# FD-01_MK3.net
KiCad netlist of a schematic drawn in EasyEDA
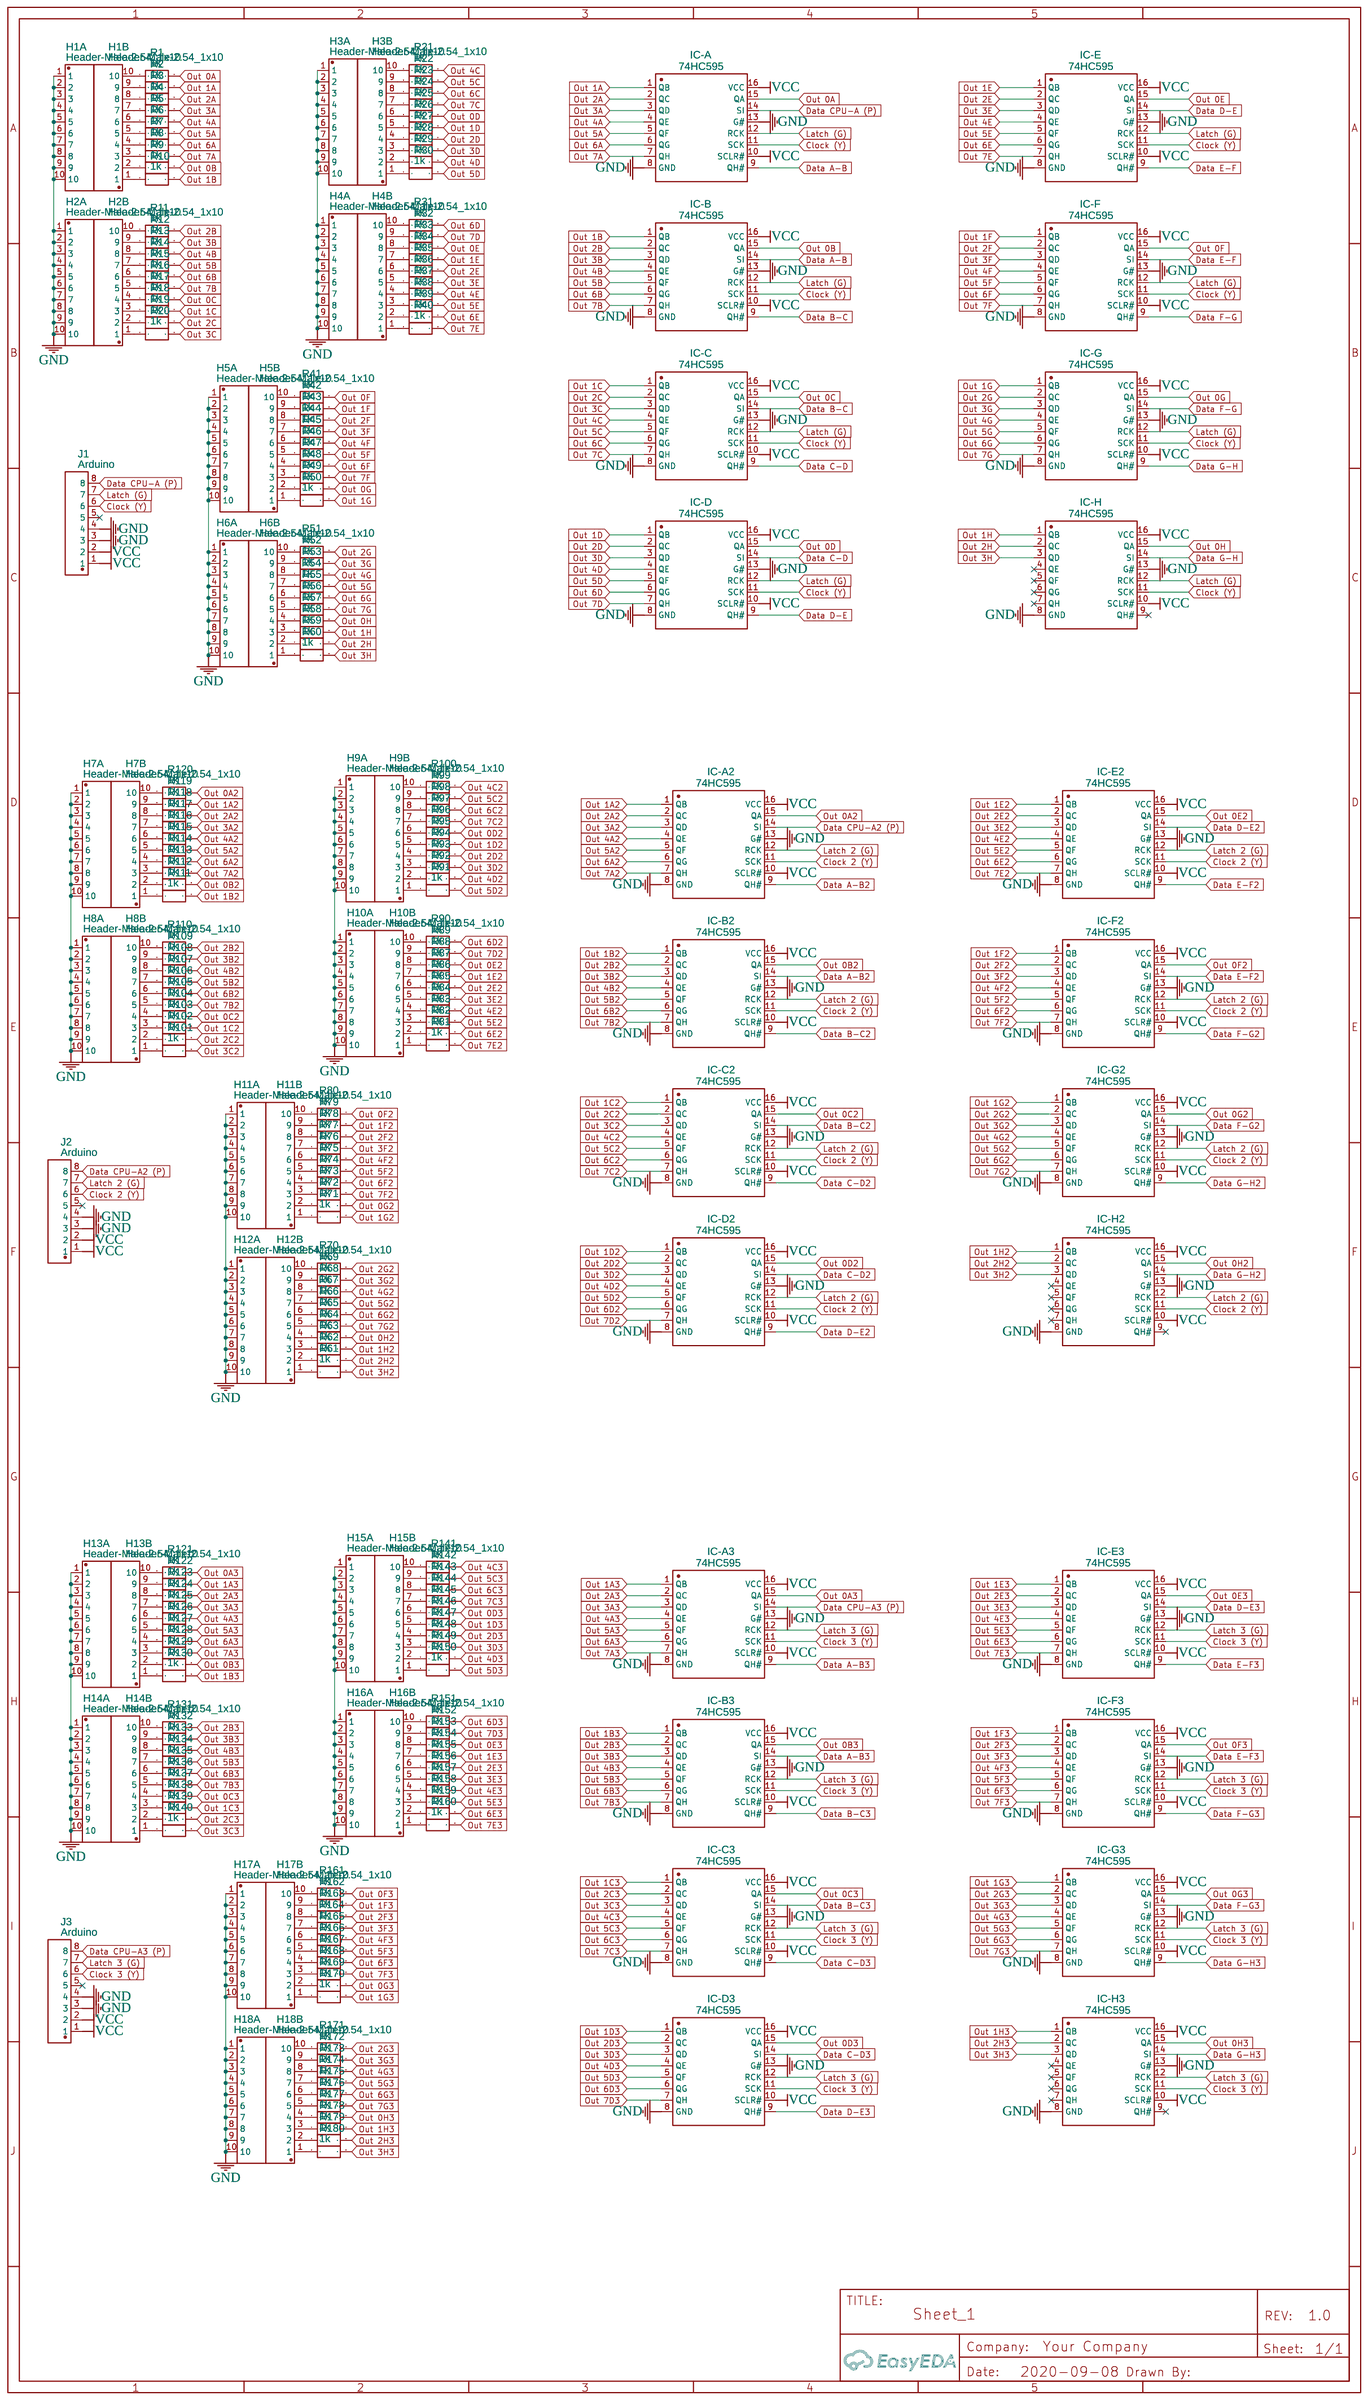
[diagram p0: schematic sheet]

(export (version "E")
  (design (tool "Eeschema 10.0.6"))
  (components
    (comp (ref "H1A")
      (value "Header-Male-2.54_1x10")
      (fields
        (field (name "BOM_Manufacturer Part") "Headers  Pins2.54mm1*10P")
        (field (name "BOM_Supplier Part") "C57369")
      )
      (libsource (lib "") (part "Header-Male-2.54_1x10_16"))
    )
    (comp (ref "H1B")
      (value "Header-Male-2.54_1x10")
      (fields
        (field (name "BOM_Manufacturer Part") "Headers  Pins2.54mm1*10P")
        (field (name "BOM_Supplier Part") "C57369")
      )
      (libsource (lib "") (part "Header-Male-2.54_1x10_34"))
    )
    (comp (ref "H2A")
      (value "Header-Male-2.54_1x10")
      (fields
        (field (name "BOM_Manufacturer Part") "Headers  Pins2.54mm1*10P")
        (field (name "BOM_Supplier Part") "C57369")
      )
      (libsource (lib "") (part "Header-Male-2.54_1x10_31"))
    )
    (comp (ref "H2B")
      (value "Header-Male-2.54_1x10")
      (fields
        (field (name "BOM_Manufacturer Part") "Headers  Pins2.54mm1*10P")
        (field (name "BOM_Supplier Part") "C57369")
      )
      (libsource (lib "") (part "Header-Male-2.54_1x10_8"))
    )
    (comp (ref "H3A")
      (value "Header-Male-2.54_1x10")
      (fields
        (field (name "BOM_Manufacturer Part") "Headers  Pins2.54mm1*10P")
        (field (name "BOM_Supplier Part") "C57369")
      )
      (libsource (lib "") (part "Header-Male-2.54_1x10_15"))
    )
    (comp (ref "H3B")
      (value "Header-Male-2.54_1x10")
      (fields
        (field (name "BOM_Manufacturer Part") "Headers  Pins2.54mm1*10P")
        (field (name "BOM_Supplier Part") "C57369")
      )
      (libsource (lib "") (part "Header-Male-2.54_1x10_9"))
    )
    (comp (ref "H4A")
      (value "Header-Male-2.54_1x10")
      (fields
        (field (name "BOM_Manufacturer Part") "Headers  Pins2.54mm1*10P")
        (field (name "BOM_Supplier Part") "C57369")
      )
      (libsource (lib "") (part "Header-Male-2.54_1x10_23"))
    )
    (comp (ref "H4B")
      (value "Header-Male-2.54_1x10")
      (fields
        (field (name "BOM_Manufacturer Part") "Headers  Pins2.54mm1*10P")
        (field (name "BOM_Supplier Part") "C57369")
      )
      (libsource (lib "") (part "Header-Male-2.54_1x10_27"))
    )
    (comp (ref "H5A")
      (value "Header-Male-2.54_1x10")
      (fields
        (field (name "BOM_Manufacturer Part") "Headers  Pins2.54mm1*10P")
        (field (name "BOM_Supplier Part") "C57369")
      )
      (libsource (lib "") (part "Header-Male-2.54_1x10_22"))
    )
    (comp (ref "H5B")
      (value "Header-Male-2.54_1x10")
      (fields
        (field (name "BOM_Manufacturer Part") "Headers  Pins2.54mm1*10P")
        (field (name "BOM_Supplier Part") "C57369")
      )
      (libsource (lib "") (part "Header-Male-2.54_1x10_19"))
    )
    (comp (ref "H6A")
      (value "Header-Male-2.54_1x10")
      (fields
        (field (name "BOM_Manufacturer Part") "Headers  Pins2.54mm1*10P")
        (field (name "BOM_Supplier Part") "C57369")
      )
      (libsource (lib "") (part "Header-Male-2.54_1x10_25"))
    )
    (comp (ref "H6B")
      (value "Header-Male-2.54_1x10")
      (fields
        (field (name "BOM_Manufacturer Part") "Headers  Pins2.54mm1*10P")
        (field (name "BOM_Supplier Part") "C57369")
      )
      (libsource (lib "") (part "Header-Male-2.54_1x10_24"))
    )
    (comp (ref "H7A")
      (value "Header-Male-2.54_1x10")
      (fields
        (field (name "BOM_Manufacturer Part") "Headers  Pins2.54mm1*10P")
        (field (name "BOM_Supplier Part") "C57369")
      )
      (libsource (lib "") (part "Header-Male-2.54_1x10_30"))
    )
    (comp (ref "H7B")
      (value "Header-Male-2.54_1x10")
      (fields
        (field (name "BOM_Manufacturer Part") "Headers  Pins2.54mm1*10P")
        (field (name "BOM_Supplier Part") "C57369")
      )
      (libsource (lib "") (part "Header-Male-2.54_1x10_29"))
    )
    (comp (ref "H8A")
      (value "Header-Male-2.54_1x10")
      (fields
        (field (name "BOM_Manufacturer Part") "Headers  Pins2.54mm1*10P")
        (field (name "BOM_Supplier Part") "C57369")
      )
      (libsource (lib "") (part "Header-Male-2.54_1x10_32"))
    )
    (comp (ref "H8B")
      (value "Header-Male-2.54_1x10")
      (fields
        (field (name "BOM_Manufacturer Part") "Headers  Pins2.54mm1*10P")
        (field (name "BOM_Supplier Part") "C57369")
      )
      (libsource (lib "") (part "Header-Male-2.54_1x10_21"))
    )
    (comp (ref "H9A")
      (value "Header-Male-2.54_1x10")
      (fields
        (field (name "BOM_Manufacturer Part") "Headers  Pins2.54mm1*10P")
        (field (name "BOM_Supplier Part") "C57369")
      )
      (libsource (lib "") (part "Header-Male-2.54_1x10_13"))
    )
    (comp (ref "H9B")
      (value "Header-Male-2.54_1x10")
      (fields
        (field (name "BOM_Manufacturer Part") "Headers  Pins2.54mm1*10P")
        (field (name "BOM_Supplier Part") "C57369")
      )
      (libsource (lib "") (part "Header-Male-2.54_1x10_33"))
    )
    (comp (ref "H10A")
      (value "Header-Male-2.54_1x10")
      (fields
        (field (name "BOM_Manufacturer Part") "Headers  Pins2.54mm1*10P")
        (field (name "BOM_Supplier Part") "C57369")
      )
      (libsource (lib "") (part "Header-Male-2.54_1x10"))
    )
    (comp (ref "H10B")
      (value "Header-Male-2.54_1x10")
      (fields
        (field (name "BOM_Manufacturer Part") "Headers  Pins2.54mm1*10P")
        (field (name "BOM_Supplier Part") "C57369")
      )
      (libsource (lib "") (part "Header-Male-2.54_1x10_18"))
    )
    (comp (ref "H11A")
      (value "Header-Male-2.54_1x10")
      (fields
        (field (name "BOM_Manufacturer Part") "Headers  Pins2.54mm1*10P")
        (field (name "BOM_Supplier Part") "C57369")
      )
      (libsource (lib "") (part "Header-Male-2.54_1x10_1"))
    )
    (comp (ref "H11B")
      (value "Header-Male-2.54_1x10")
      (fields
        (field (name "BOM_Manufacturer Part") "Headers  Pins2.54mm1*10P")
        (field (name "BOM_Supplier Part") "C57369")
      )
      (libsource (lib "") (part "Header-Male-2.54_1x10_26"))
    )
    (comp (ref "H12A")
      (value "Header-Male-2.54_1x10")
      (fields
        (field (name "BOM_Manufacturer Part") "Headers  Pins2.54mm1*10P")
        (field (name "BOM_Supplier Part") "C57369")
      )
      (libsource (lib "") (part "Header-Male-2.54_1x10_5"))
    )
    (comp (ref "H12B")
      (value "Header-Male-2.54_1x10")
      (fields
        (field (name "BOM_Manufacturer Part") "Headers  Pins2.54mm1*10P")
        (field (name "BOM_Supplier Part") "C57369")
      )
      (libsource (lib "") (part "Header-Male-2.54_1x10_6"))
    )
    (comp (ref "H13A")
      (value "Header-Male-2.54_1x10")
      (fields
        (field (name "BOM_Manufacturer Part") "Headers  Pins2.54mm1*10P")
        (field (name "BOM_Supplier Part") "C57369")
      )
      (libsource (lib "") (part "Header-Male-2.54_1x10_20"))
    )
    (comp (ref "H13B")
      (value "Header-Male-2.54_1x10")
      (fields
        (field (name "BOM_Manufacturer Part") "Headers  Pins2.54mm1*10P")
        (field (name "BOM_Supplier Part") "C57369")
      )
      (libsource (lib "") (part "Header-Male-2.54_1x10_7"))
    )
    (comp (ref "H14A")
      (value "Header-Male-2.54_1x10")
      (fields
        (field (name "BOM_Manufacturer Part") "Headers  Pins2.54mm1*10P")
        (field (name "BOM_Supplier Part") "C57369")
      )
      (libsource (lib "") (part "Header-Male-2.54_1x10_35"))
    )
    (comp (ref "H14B")
      (value "Header-Male-2.54_1x10")
      (fields
        (field (name "BOM_Manufacturer Part") "Headers  Pins2.54mm1*10P")
        (field (name "BOM_Supplier Part") "C57369")
      )
      (libsource (lib "") (part "Header-Male-2.54_1x10_4"))
    )
    (comp (ref "H15A")
      (value "Header-Male-2.54_1x10")
      (fields
        (field (name "BOM_Manufacturer Part") "Headers  Pins2.54mm1*10P")
        (field (name "BOM_Supplier Part") "C57369")
      )
      (libsource (lib "") (part "Header-Male-2.54_1x10_12"))
    )
    (comp (ref "H15B")
      (value "Header-Male-2.54_1x10")
      (fields
        (field (name "BOM_Manufacturer Part") "Headers  Pins2.54mm1*10P")
        (field (name "BOM_Supplier Part") "C57369")
      )
      (libsource (lib "") (part "Header-Male-2.54_1x10_14"))
    )
    (comp (ref "H16A")
      (value "Header-Male-2.54_1x10")
      (fields
        (field (name "BOM_Manufacturer Part") "Headers  Pins2.54mm1*10P")
        (field (name "BOM_Supplier Part") "C57369")
      )
      (libsource (lib "") (part "Header-Male-2.54_1x10_11"))
    )
    (comp (ref "H16B")
      (value "Header-Male-2.54_1x10")
      (fields
        (field (name "BOM_Manufacturer Part") "Headers  Pins2.54mm1*10P")
        (field (name "BOM_Supplier Part") "C57369")
      )
      (libsource (lib "") (part "Header-Male-2.54_1x10_10"))
    )
    (comp (ref "H17A")
      (value "Header-Male-2.54_1x10")
      (fields
        (field (name "BOM_Manufacturer Part") "Headers  Pins2.54mm1*10P")
        (field (name "BOM_Supplier Part") "C57369")
      )
      (libsource (lib "") (part "Header-Male-2.54_1x10_3"))
    )
    (comp (ref "H17B")
      (value "Header-Male-2.54_1x10")
      (fields
        (field (name "BOM_Manufacturer Part") "Headers  Pins2.54mm1*10P")
        (field (name "BOM_Supplier Part") "C57369")
      )
      (libsource (lib "") (part "Header-Male-2.54_1x10_28"))
    )
    (comp (ref "H18A")
      (value "Header-Male-2.54_1x10")
      (fields
        (field (name "BOM_Manufacturer Part") "Headers  Pins2.54mm1*10P")
        (field (name "BOM_Supplier Part") "C57369")
      )
      (libsource (lib "") (part "Header-Male-2.54_1x10_17"))
    )
    (comp (ref "H18B")
      (value "Header-Male-2.54_1x10")
      (fields
        (field (name "BOM_Manufacturer Part") "Headers  Pins2.54mm1*10P")
        (field (name "BOM_Supplier Part") "C57369")
      )
      (libsource (lib "") (part "Header-Male-2.54_1x10_2"))
    )
    (comp (ref "IC-A")
      (value "74HC595")
      (fields (field (name "BOM_Manufacturer Part") "74HC595D") (field (name "BOM_Supplier Part") "C86609"))
      (libsource (lib "") (part "74HC595D_7"))
    )
    (comp (ref "IC-A2")
      (value "74HC595")
      (fields (field (name "BOM_Manufacturer Part") "74HC595D") (field (name "BOM_Supplier Part") "C86609"))
      (libsource (lib "") (part "74HC595D_7"))
    )
    (comp (ref "IC-A3")
      (value "74HC595")
      (fields (field (name "BOM_Manufacturer Part") "74HC595D") (field (name "BOM_Supplier Part") "C86609"))
      (libsource (lib "") (part "74HC595D_7"))
    )
    (comp (ref "IC-B")
      (value "74HC595")
      (fields (field (name "BOM_Manufacturer Part") "74HC595D") (field (name "BOM_Supplier Part") "C86609"))
      (libsource (lib "") (part "74HC595D_6"))
    )
    (comp (ref "IC-B2")
      (value "74HC595")
      (fields (field (name "BOM_Manufacturer Part") "74HC595D") (field (name "BOM_Supplier Part") "C86609"))
      (libsource (lib "") (part "74HC595D_6"))
    )
    (comp (ref "IC-B3")
      (value "74HC595")
      (fields (field (name "BOM_Manufacturer Part") "74HC595D") (field (name "BOM_Supplier Part") "C86609"))
      (libsource (lib "") (part "74HC595D_6"))
    )
    (comp (ref "IC-C")
      (value "74HC595")
      (fields (field (name "BOM_Manufacturer Part") "74HC595D") (field (name "BOM_Supplier Part") "C86609"))
      (libsource (lib "") (part "74HC595D_2"))
    )
    (comp (ref "IC-C2")
      (value "74HC595")
      (fields (field (name "BOM_Manufacturer Part") "74HC595D") (field (name "BOM_Supplier Part") "C86609"))
      (libsource (lib "") (part "74HC595D_2"))
    )
    (comp (ref "IC-C3")
      (value "74HC595")
      (fields (field (name "BOM_Manufacturer Part") "74HC595D") (field (name "BOM_Supplier Part") "C86609"))
      (libsource (lib "") (part "74HC595D_2"))
    )
    (comp (ref "IC-D")
      (value "74HC595")
      (fields (field (name "BOM_Manufacturer Part") "74HC595D") (field (name "BOM_Supplier Part") "C86609"))
      (libsource (lib "") (part "74HC595D_3"))
    )
    (comp (ref "IC-D2")
      (value "74HC595")
      (fields (field (name "BOM_Manufacturer Part") "74HC595D") (field (name "BOM_Supplier Part") "C86609"))
      (libsource (lib "") (part "74HC595D_3"))
    )
    (comp (ref "IC-D3")
      (value "74HC595")
      (fields (field (name "BOM_Manufacturer Part") "74HC595D") (field (name "BOM_Supplier Part") "C86609"))
      (libsource (lib "") (part "74HC595D_3"))
    )
    (comp (ref "IC-E")
      (value "74HC595")
      (fields (field (name "BOM_Manufacturer Part") "74HC595D") (field (name "BOM_Supplier Part") "C86609"))
      (libsource (lib "") (part "74HC595D"))
    )
    (comp (ref "IC-E2")
      (value "74HC595")
      (fields (field (name "BOM_Manufacturer Part") "74HC595D") (field (name "BOM_Supplier Part") "C86609"))
      (libsource (lib "") (part "74HC595D"))
    )
    (comp (ref "IC-E3")
      (value "74HC595")
      (fields (field (name "BOM_Manufacturer Part") "74HC595D") (field (name "BOM_Supplier Part") "C86609"))
      (libsource (lib "") (part "74HC595D"))
    )
    (comp (ref "IC-F")
      (value "74HC595")
      (fields (field (name "BOM_Manufacturer Part") "74HC595D") (field (name "BOM_Supplier Part") "C86609"))
      (libsource (lib "") (part "74HC595D_1"))
    )
    (comp (ref "IC-F2")
      (value "74HC595")
      (fields (field (name "BOM_Manufacturer Part") "74HC595D") (field (name "BOM_Supplier Part") "C86609"))
      (libsource (lib "") (part "74HC595D_1"))
    )
    (comp (ref "IC-F3")
      (value "74HC595")
      (fields (field (name "BOM_Manufacturer Part") "74HC595D") (field (name "BOM_Supplier Part") "C86609"))
      (libsource (lib "") (part "74HC595D_1"))
    )
    (comp (ref "IC-G")
      (value "74HC595")
      (fields (field (name "BOM_Manufacturer Part") "74HC595D") (field (name "BOM_Supplier Part") "C86609"))
      (libsource (lib "") (part "74HC595D_4"))
    )
    (comp (ref "IC-G2")
      (value "74HC595")
      (fields (field (name "BOM_Manufacturer Part") "74HC595D") (field (name "BOM_Supplier Part") "C86609"))
      (libsource (lib "") (part "74HC595D_4"))
    )
    (comp (ref "IC-G3")
      (value "74HC595")
      (fields (field (name "BOM_Manufacturer Part") "74HC595D") (field (name "BOM_Supplier Part") "C86609"))
      (libsource (lib "") (part "74HC595D_4"))
    )
    (comp (ref "IC-H")
      (value "74HC595")
      (fields (field (name "BOM_Manufacturer Part") "74HC595D") (field (name "BOM_Supplier Part") "C86609"))
      (libsource (lib "") (part "74HC595D_5"))
    )
    (comp (ref "IC-H2")
      (value "74HC595")
      (fields (field (name "BOM_Manufacturer Part") "74HC595D") (field (name "BOM_Supplier Part") "C86609"))
      (libsource (lib "") (part "74HC595D_5"))
    )
    (comp (ref "IC-H3")
      (value "74HC595")
      (fields (field (name "BOM_Manufacturer Part") "74HC595D") (field (name "BOM_Supplier Part") "C86609"))
      (libsource (lib "") (part "74HC595D_5"))
    )
    (comp (ref "J1")
      (value "Arduino")
      (fields
        (field (name "BOM_Manufacturer Part") "Header2.54mm 1*8P")
        (field (name "BOM_Supplier Part") "C49256")
      )
      (libsource (lib "") (part "Header2.54mm 1*8P"))
    )
    (comp (ref "J2")
      (value "Arduino")
      (fields
        (field (name "BOM_Manufacturer Part") "Header2.54mm 1*8P")
        (field (name "BOM_Supplier Part") "C49256")
      )
      (libsource (lib "") (part "Header2.54mm 1*8P"))
    )
    (comp (ref "J3")
      (value "Arduino")
      (fields
        (field (name "BOM_Manufacturer Part") "Header2.54mm 1*8P")
        (field (name "BOM_Supplier Part") "C49256")
      )
      (libsource (lib "") (part "Header2.54mm 1*8P"))
    )
    (comp (ref "R1") (value "1k") (libsource (lib "") (part "R_0603_EU")))
    (comp (ref "R2") (value "1k") (libsource (lib "") (part "R_0603_EU")))
    (comp (ref "R3") (value "1k") (libsource (lib "") (part "R_0603_EU")))
    (comp (ref "R4") (value "1k") (libsource (lib "") (part "R_0603_EU")))
    (comp (ref "R5") (value "1k") (libsource (lib "") (part "R_0603_EU")))
    (comp (ref "R6") (value "1k") (libsource (lib "") (part "R_0603_EU")))
    (comp (ref "R7") (value "1k") (libsource (lib "") (part "R_0603_EU")))
    (comp (ref "R8") (value "1k") (libsource (lib "") (part "R_0603_EU")))
    (comp (ref "R9") (value "1k") (libsource (lib "") (part "R_0603_EU")))
    (comp (ref "R10") (value "1k") (libsource (lib "") (part "R_0603_EU")))
    (comp (ref "R11") (value "1k") (libsource (lib "") (part "R_0603_EU")))
    (comp (ref "R12") (value "1k") (libsource (lib "") (part "R_0603_EU")))
    (comp (ref "R13") (value "1k") (libsource (lib "") (part "R_0603_EU")))
    (comp (ref "R14") (value "1k") (libsource (lib "") (part "R_0603_EU")))
    (comp (ref "R15") (value "1k") (libsource (lib "") (part "R_0603_EU")))
    (comp (ref "R16") (value "1k") (libsource (lib "") (part "R_0603_EU")))
    (comp (ref "R17") (value "1k") (libsource (lib "") (part "R_0603_EU")))
    (comp (ref "R18") (value "1k") (libsource (lib "") (part "R_0603_EU")))
    (comp (ref "R19") (value "1k") (libsource (lib "") (part "R_0603_EU")))
    (comp (ref "R20") (value "1k") (libsource (lib "") (part "R_0603_EU")))
    (comp (ref "R21") (value "1k") (libsource (lib "") (part "R_0603_EU")))
    (comp (ref "R22") (value "1k") (libsource (lib "") (part "R_0603_EU")))
    (comp (ref "R23") (value "1k") (libsource (lib "") (part "R_0603_EU")))
    (comp (ref "R24") (value "1k") (libsource (lib "") (part "R_0603_EU")))
    (comp (ref "R25") (value "1k") (libsource (lib "") (part "R_0603_EU")))
    (comp (ref "R26") (value "1k") (libsource (lib "") (part "R_0603_EU")))
    (comp (ref "R27") (value "1k") (libsource (lib "") (part "R_0603_EU")))
    (comp (ref "R28") (value "1k") (libsource (lib "") (part "R_0603_EU")))
    (comp (ref "R29") (value "1k") (libsource (lib "") (part "R_0603_EU")))
    (comp (ref "R30") (value "1k") (libsource (lib "") (part "R_0603_EU")))
    (comp (ref "R31") (value "1k") (libsource (lib "") (part "R_0603_EU")))
    (comp (ref "R32") (value "1k") (libsource (lib "") (part "R_0603_EU")))
    (comp (ref "R33") (value "1k") (libsource (lib "") (part "R_0603_EU")))
    (comp (ref "R34") (value "1k") (libsource (lib "") (part "R_0603_EU")))
    (comp (ref "R35") (value "1k") (libsource (lib "") (part "R_0603_EU")))
    (comp (ref "R36") (value "1k") (libsource (lib "") (part "R_0603_EU")))
    (comp (ref "R37") (value "1k") (libsource (lib "") (part "R_0603_EU")))
    (comp (ref "R38") (value "1k") (libsource (lib "") (part "R_0603_EU")))
    (comp (ref "R39") (value "1k") (libsource (lib "") (part "R_0603_EU")))
    (comp (ref "R40") (value "1k") (libsource (lib "") (part "R_0603_EU")))
    (comp (ref "R41") (value "1k") (libsource (lib "") (part "R_0603_EU")))
    (comp (ref "R42") (value "1k") (libsource (lib "") (part "R_0603_EU")))
    (comp (ref "R43") (value "1k") (libsource (lib "") (part "R_0603_EU")))
    (comp (ref "R44") (value "1k") (libsource (lib "") (part "R_0603_EU")))
    (comp (ref "R45") (value "1k") (libsource (lib "") (part "R_0603_EU")))
    (comp (ref "R46") (value "1k") (libsource (lib "") (part "R_0603_EU")))
    (comp (ref "R47") (value "1k") (libsource (lib "") (part "R_0603_EU")))
    (comp (ref "R48") (value "1k") (libsource (lib "") (part "R_0603_EU")))
    (comp (ref "R49") (value "1k") (libsource (lib "") (part "R_0603_EU")))
    (comp (ref "R50") (value "1k") (libsource (lib "") (part "R_0603_EU")))
    (comp (ref "R51") (value "1k") (libsource (lib "") (part "R_0603_EU")))
    (comp (ref "R52") (value "1k") (libsource (lib "") (part "R_0603_EU")))
    (comp (ref "R53") (value "1k") (libsource (lib "") (part "R_0603_EU")))
    (comp (ref "R54") (value "1k") (libsource (lib "") (part "R_0603_EU")))
    (comp (ref "R55") (value "1k") (libsource (lib "") (part "R_0603_EU")))
    (comp (ref "R56") (value "1k") (libsource (lib "") (part "R_0603_EU")))
    (comp (ref "R57") (value "1k") (libsource (lib "") (part "R_0603_EU")))
    (comp (ref "R58") (value "1k") (libsource (lib "") (part "R_0603_EU")))
    (comp (ref "R59") (value "1k") (libsource (lib "") (part "R_0603_EU")))
    (comp (ref "R60") (value "1k") (libsource (lib "") (part "R_0603_EU")))
    (comp (ref "R61") (value "1k") (libsource (lib "") (part "R_0603_EU")))
    (comp (ref "R62") (value "1k") (libsource (lib "") (part "R_0603_EU")))
    (comp (ref "R63") (value "1k") (libsource (lib "") (part "R_0603_EU")))
    (comp (ref "R64") (value "1k") (libsource (lib "") (part "R_0603_EU")))
    (comp (ref "R65") (value "1k") (libsource (lib "") (part "R_0603_EU")))
    (comp (ref "R66") (value "1k") (libsource (lib "") (part "R_0603_EU")))
    (comp (ref "R67") (value "1k") (libsource (lib "") (part "R_0603_EU")))
    (comp (ref "R68") (value "1k") (libsource (lib "") (part "R_0603_EU")))
    (comp (ref "R69") (value "1k") (libsource (lib "") (part "R_0603_EU")))
    (comp (ref "R70") (value "1k") (libsource (lib "") (part "R_0603_EU")))
    (comp (ref "R71") (value "1k") (libsource (lib "") (part "R_0603_EU")))
    (comp (ref "R72") (value "1k") (libsource (lib "") (part "R_0603_EU")))
    (comp (ref "R73") (value "1k") (libsource (lib "") (part "R_0603_EU")))
    (comp (ref "R74") (value "1k") (libsource (lib "") (part "R_0603_EU")))
    (comp (ref "R75") (value "1k") (libsource (lib "") (part "R_0603_EU")))
    (comp (ref "R76") (value "1k") (libsource (lib "") (part "R_0603_EU")))
    (comp (ref "R77") (value "1k") (libsource (lib "") (part "R_0603_EU")))
    (comp (ref "R78") (value "1k") (libsource (lib "") (part "R_0603_EU")))
    (comp (ref "R79") (value "1k") (libsource (lib "") (part "R_0603_EU")))
    (comp (ref "R80") (value "1k") (libsource (lib "") (part "R_0603_EU")))
    (comp (ref "R81") (value "1k") (libsource (lib "") (part "R_0603_EU")))
    (comp (ref "R82") (value "1k") (libsource (lib "") (part "R_0603_EU")))
    (comp (ref "R83") (value "1k") (libsource (lib "") (part "R_0603_EU")))
    (comp (ref "R84") (value "1k") (libsource (lib "") (part "R_0603_EU")))
    (comp (ref "R85") (value "1k") (libsource (lib "") (part "R_0603_EU")))
    (comp (ref "R86") (value "1k") (libsource (lib "") (part "R_0603_EU")))
    (comp (ref "R87") (value "1k") (libsource (lib "") (part "R_0603_EU")))
    (comp (ref "R88") (value "1k") (libsource (lib "") (part "R_0603_EU")))
    (comp (ref "R89") (value "1k") (libsource (lib "") (part "R_0603_EU")))
    (comp (ref "R90") (value "1k") (libsource (lib "") (part "R_0603_EU")))
    (comp (ref "R91") (value "1k") (libsource (lib "") (part "R_0603_EU")))
    (comp (ref "R92") (value "1k") (libsource (lib "") (part "R_0603_EU")))
    (comp (ref "R93") (value "1k") (libsource (lib "") (part "R_0603_EU")))
    (comp (ref "R94") (value "1k") (libsource (lib "") (part "R_0603_EU")))
    (comp (ref "R95") (value "1k") (libsource (lib "") (part "R_0603_EU")))
    (comp (ref "R96") (value "1k") (libsource (lib "") (part "R_0603_EU")))
    (comp (ref "R97") (value "1k") (libsource (lib "") (part "R_0603_EU")))
    (comp (ref "R98") (value "1k") (libsource (lib "") (part "R_0603_EU")))
    (comp (ref "R99") (value "1k") (libsource (lib "") (part "R_0603_EU")))
    (comp (ref "R100") (value "1k") (libsource (lib "") (part "R_0603_EU")))
    (comp (ref "R101") (value "1k") (libsource (lib "") (part "R_0603_EU")))
    (comp (ref "R102") (value "1k") (libsource (lib "") (part "R_0603_EU")))
    (comp (ref "R103") (value "1k") (libsource (lib "") (part "R_0603_EU")))
    (comp (ref "R104") (value "1k") (libsource (lib "") (part "R_0603_EU")))
    (comp (ref "R105") (value "1k") (libsource (lib "") (part "R_0603_EU")))
    (comp (ref "R106") (value "1k") (libsource (lib "") (part "R_0603_EU")))
    (comp (ref "R107") (value "1k") (libsource (lib "") (part "R_0603_EU")))
    (comp (ref "R108") (value "1k") (libsource (lib "") (part "R_0603_EU")))
    (comp (ref "R109") (value "1k") (libsource (lib "") (part "R_0603_EU")))
    (comp (ref "R110") (value "1k") (libsource (lib "") (part "R_0603_EU")))
    (comp (ref "R111") (value "1k") (libsource (lib "") (part "R_0603_EU")))
    (comp (ref "R112") (value "1k") (libsource (lib "") (part "R_0603_EU")))
    (comp (ref "R113") (value "1k") (libsource (lib "") (part "R_0603_EU")))
    (comp (ref "R114") (value "1k") (libsource (lib "") (part "R_0603_EU")))
    (comp (ref "R115") (value "1k") (libsource (lib "") (part "R_0603_EU")))
    (comp (ref "R116") (value "1k") (libsource (lib "") (part "R_0603_EU")))
    (comp (ref "R117") (value "1k") (libsource (lib "") (part "R_0603_EU")))
    (comp (ref "R118") (value "1k") (libsource (lib "") (part "R_0603_EU")))
    (comp (ref "R119") (value "1k") (libsource (lib "") (part "R_0603_EU")))
    (comp (ref "R120") (value "1k") (libsource (lib "") (part "R_0603_EU")))
    (comp (ref "R121") (value "1k") (libsource (lib "") (part "R_0603_EU")))
    (comp (ref "R122") (value "1k") (libsource (lib "") (part "R_0603_EU")))
    (comp (ref "R123") (value "1k") (libsource (lib "") (part "R_0603_EU")))
    (comp (ref "R124") (value "1k") (libsource (lib "") (part "R_0603_EU")))
    (comp (ref "R125") (value "1k") (libsource (lib "") (part "R_0603_EU")))
    (comp (ref "R126") (value "1k") (libsource (lib "") (part "R_0603_EU")))
    (comp (ref "R127") (value "1k") (libsource (lib "") (part "R_0603_EU")))
    (comp (ref "R128") (value "1k") (libsource (lib "") (part "R_0603_EU")))
    (comp (ref "R129") (value "1k") (libsource (lib "") (part "R_0603_EU")))
    (comp (ref "R130") (value "1k") (libsource (lib "") (part "R_0603_EU")))
    (comp (ref "R131") (value "1k") (libsource (lib "") (part "R_0603_EU")))
    (comp (ref "R132") (value "1k") (libsource (lib "") (part "R_0603_EU")))
    (comp (ref "R133") (value "1k") (libsource (lib "") (part "R_0603_EU")))
    (comp (ref "R134") (value "1k") (libsource (lib "") (part "R_0603_EU")))
    (comp (ref "R135") (value "1k") (libsource (lib "") (part "R_0603_EU")))
    (comp (ref "R136") (value "1k") (libsource (lib "") (part "R_0603_EU")))
    (comp (ref "R137") (value "1k") (libsource (lib "") (part "R_0603_EU")))
    (comp (ref "R138") (value "1k") (libsource (lib "") (part "R_0603_EU")))
    (comp (ref "R139") (value "1k") (libsource (lib "") (part "R_0603_EU")))
    (comp (ref "R140") (value "1k") (libsource (lib "") (part "R_0603_EU")))
    (comp (ref "R141") (value "1k") (libsource (lib "") (part "R_0603_EU")))
    (comp (ref "R142") (value "1k") (libsource (lib "") (part "R_0603_EU")))
    (comp (ref "R143") (value "1k") (libsource (lib "") (part "R_0603_EU")))
    (comp (ref "R144") (value "1k") (libsource (lib "") (part "R_0603_EU")))
    (comp (ref "R145") (value "1k") (libsource (lib "") (part "R_0603_EU")))
    (comp (ref "R146") (value "1k") (libsource (lib "") (part "R_0603_EU")))
    (comp (ref "R147") (value "1k") (libsource (lib "") (part "R_0603_EU")))
    (comp (ref "R148") (value "1k") (libsource (lib "") (part "R_0603_EU")))
    (comp (ref "R149") (value "1k") (libsource (lib "") (part "R_0603_EU")))
    (comp (ref "R150") (value "1k") (libsource (lib "") (part "R_0603_EU")))
    (comp (ref "R151") (value "1k") (libsource (lib "") (part "R_0603_EU")))
    (comp (ref "R152") (value "1k") (libsource (lib "") (part "R_0603_EU")))
    (comp (ref "R153") (value "1k") (libsource (lib "") (part "R_0603_EU")))
    (comp (ref "R154") (value "1k") (libsource (lib "") (part "R_0603_EU")))
    (comp (ref "R155") (value "1k") (libsource (lib "") (part "R_0603_EU")))
    (comp (ref "R156") (value "1k") (libsource (lib "") (part "R_0603_EU")))
    (comp (ref "R157") (value "1k") (libsource (lib "") (part "R_0603_EU")))
    (comp (ref "R158") (value "1k") (libsource (lib "") (part "R_0603_EU")))
    (comp (ref "R159") (value "1k") (libsource (lib "") (part "R_0603_EU")))
    (comp (ref "R160") (value "1k") (libsource (lib "") (part "R_0603_EU")))
    (comp (ref "R161") (value "1k") (libsource (lib "") (part "R_0603_EU")))
    (comp (ref "R162") (value "1k") (libsource (lib "") (part "R_0603_EU")))
    (comp (ref "R163") (value "1k") (libsource (lib "") (part "R_0603_EU")))
    (comp (ref "R164") (value "1k") (libsource (lib "") (part "R_0603_EU")))
    (comp (ref "R165") (value "1k") (libsource (lib "") (part "R_0603_EU")))
    (comp (ref "R166") (value "1k") (libsource (lib "") (part "R_0603_EU")))
    (comp (ref "R167") (value "1k") (libsource (lib "") (part "R_0603_EU")))
    (comp (ref "R168") (value "1k") (libsource (lib "") (part "R_0603_EU")))
    (comp (ref "R169") (value "1k") (libsource (lib "") (part "R_0603_EU")))
    (comp (ref "R170") (value "1k") (libsource (lib "") (part "R_0603_EU")))
    (comp (ref "R171") (value "1k") (libsource (lib "") (part "R_0603_EU")))
    (comp (ref "R172") (value "1k") (libsource (lib "") (part "R_0603_EU")))
    (comp (ref "R173") (value "1k") (libsource (lib "") (part "R_0603_EU")))
    (comp (ref "R174") (value "1k") (libsource (lib "") (part "R_0603_EU")))
    (comp (ref "R175") (value "1k") (libsource (lib "") (part "R_0603_EU")))
    (comp (ref "R176") (value "1k") (libsource (lib "") (part "R_0603_EU")))
    (comp (ref "R177") (value "1k") (libsource (lib "") (part "R_0603_EU")))
    (comp (ref "R178") (value "1k") (libsource (lib "") (part "R_0603_EU")))
    (comp (ref "R179") (value "1k") (libsource (lib "") (part "R_0603_EU")))
    (comp (ref "R180") (value "1k") (libsource (lib "") (part "R_0603_EU")))
  )
  (nets
    (net (code "1") (name "Clock (Y)") (class "Default")
      (node (ref "IC-A") (pin "11") (pinfunction "SCK_11") (pintype "unspecified"))
      (node (ref "IC-B") (pin "11") (pinfunction "SCK_11") (pintype "unspecified"))
      (node (ref "IC-C") (pin "11") (pinfunction "SCK_11") (pintype "unspecified"))
      (node (ref "IC-D") (pin "11") (pinfunction "SCK_11") (pintype "unspecified"))
      (node (ref "IC-E") (pin "11") (pinfunction "SCK_11") (pintype "unspecified"))
      (node (ref "IC-F") (pin "11") (pinfunction "SCK_11") (pintype "unspecified"))
      (node (ref "IC-G") (pin "11") (pinfunction "SCK_11") (pintype "unspecified"))
      (node (ref "IC-H") (pin "11") (pinfunction "SCK_11") (pintype "unspecified"))
      (node (ref "J1") (pin "6") (pinfunction "6_6") (pintype "unspecified"))
    )
    (net (code "2") (name "Clock 2 (Y)") (class "Default")
      (node (ref "IC-A2") (pin "11") (pinfunction "SCK_11") (pintype "unspecified"))
      (node (ref "IC-B2") (pin "11") (pinfunction "SCK_11") (pintype "unspecified"))
      (node (ref "IC-C2") (pin "11") (pinfunction "SCK_11") (pintype "unspecified"))
      (node (ref "IC-D2") (pin "11") (pinfunction "SCK_11") (pintype "unspecified"))
      (node (ref "IC-E2") (pin "11") (pinfunction "SCK_11") (pintype "unspecified"))
      (node (ref "IC-F2") (pin "11") (pinfunction "SCK_11") (pintype "unspecified"))
      (node (ref "IC-G2") (pin "11") (pinfunction "SCK_11") (pintype "unspecified"))
      (node (ref "IC-H2") (pin "11") (pinfunction "SCK_11") (pintype "unspecified"))
      (node (ref "J2") (pin "6") (pinfunction "6_6") (pintype "unspecified"))
    )
    (net (code "3") (name "Clock 3 (Y)") (class "Default")
      (node (ref "IC-A3") (pin "11") (pinfunction "SCK_11") (pintype "unspecified"))
      (node (ref "IC-B3") (pin "11") (pinfunction "SCK_11") (pintype "unspecified"))
      (node (ref "IC-C3") (pin "11") (pinfunction "SCK_11") (pintype "unspecified"))
      (node (ref "IC-D3") (pin "11") (pinfunction "SCK_11") (pintype "unspecified"))
      (node (ref "IC-E3") (pin "11") (pinfunction "SCK_11") (pintype "unspecified"))
      (node (ref "IC-F3") (pin "11") (pinfunction "SCK_11") (pintype "unspecified"))
      (node (ref "IC-G3") (pin "11") (pinfunction "SCK_11") (pintype "unspecified"))
      (node (ref "IC-H3") (pin "11") (pinfunction "SCK_11") (pintype "unspecified"))
      (node (ref "J3") (pin "6") (pinfunction "6_6") (pintype "unspecified"))
    )
    (net (code "4") (name "Data A-B") (class "Default")
      (node (ref "IC-A") (pin "9") (pinfunction "QH#_9") (pintype "unspecified"))
      (node (ref "IC-B") (pin "14") (pinfunction "SI_14") (pintype "unspecified"))
    )
    (net (code "5") (name "Data A-B2") (class "Default")
      (node (ref "IC-A2") (pin "9") (pinfunction "QH#_9") (pintype "unspecified"))
      (node (ref "IC-B2") (pin "14") (pinfunction "SI_14") (pintype "unspecified"))
    )
    (net (code "6") (name "Data A-B3") (class "Default")
      (node (ref "IC-A3") (pin "9") (pinfunction "QH#_9") (pintype "unspecified"))
      (node (ref "IC-B3") (pin "14") (pinfunction "SI_14") (pintype "unspecified"))
    )
    (net (code "7") (name "Data B-C") (class "Default")
      (node (ref "IC-B") (pin "9") (pinfunction "QH#_9") (pintype "unspecified"))
      (node (ref "IC-C") (pin "14") (pinfunction "SI_14") (pintype "unspecified"))
    )
    (net (code "8") (name "Data B-C2") (class "Default")
      (node (ref "IC-B2") (pin "9") (pinfunction "QH#_9") (pintype "unspecified"))
      (node (ref "IC-C2") (pin "14") (pinfunction "SI_14") (pintype "unspecified"))
    )
    (net (code "9") (name "Data B-C3") (class "Default")
      (node (ref "IC-B3") (pin "9") (pinfunction "QH#_9") (pintype "unspecified"))
      (node (ref "IC-C3") (pin "14") (pinfunction "SI_14") (pintype "unspecified"))
    )
    (net (code "10") (name "Data C-D") (class "Default")
      (node (ref "IC-C") (pin "9") (pinfunction "QH#_9") (pintype "unspecified"))
      (node (ref "IC-D") (pin "14") (pinfunction "SI_14") (pintype "unspecified"))
    )
    (net (code "11") (name "Data C-D2") (class "Default")
      (node (ref "IC-C2") (pin "9") (pinfunction "QH#_9") (pintype "unspecified"))
      (node (ref "IC-D2") (pin "14") (pinfunction "SI_14") (pintype "unspecified"))
    )
    (net (code "12") (name "Data C-D3") (class "Default")
      (node (ref "IC-C3") (pin "9") (pinfunction "QH#_9") (pintype "unspecified"))
      (node (ref "IC-D3") (pin "14") (pinfunction "SI_14") (pintype "unspecified"))
    )
    (net (code "13") (name "Data CPU-A (P)") (class "Default")
      (node (ref "IC-A") (pin "14") (pinfunction "SI_14") (pintype "unspecified"))
      (node (ref "J1") (pin "8") (pinfunction "8_8") (pintype "unspecified"))
    )
    (net (code "14") (name "Data CPU-A2 (P)") (class "Default")
      (node (ref "IC-A2") (pin "14") (pinfunction "SI_14") (pintype "unspecified"))
      (node (ref "J2") (pin "8") (pinfunction "8_8") (pintype "unspecified"))
    )
    (net (code "15") (name "Data CPU-A3 (P)") (class "Default")
      (node (ref "IC-A3") (pin "14") (pinfunction "SI_14") (pintype "unspecified"))
      (node (ref "J3") (pin "8") (pinfunction "8_8") (pintype "unspecified"))
    )
    (net (code "16") (name "Data D-E") (class "Default")
      (node (ref "IC-D") (pin "9") (pinfunction "QH#_9") (pintype "unspecified"))
      (node (ref "IC-E") (pin "14") (pinfunction "SI_14") (pintype "unspecified"))
    )
    (net (code "17") (name "Data D-E2") (class "Default")
      (node (ref "IC-D2") (pin "9") (pinfunction "QH#_9") (pintype "unspecified"))
      (node (ref "IC-E2") (pin "14") (pinfunction "SI_14") (pintype "unspecified"))
    )
    (net (code "18") (name "Data D-E3") (class "Default")
      (node (ref "IC-D3") (pin "9") (pinfunction "QH#_9") (pintype "unspecified"))
      (node (ref "IC-E3") (pin "14") (pinfunction "SI_14") (pintype "unspecified"))
    )
    (net (code "19") (name "Data E-F") (class "Default")
      (node (ref "IC-E") (pin "9") (pinfunction "QH#_9") (pintype "unspecified"))
      (node (ref "IC-F") (pin "14") (pinfunction "SI_14") (pintype "unspecified"))
    )
    (net (code "20") (name "Data E-F2") (class "Default")
      (node (ref "IC-E2") (pin "9") (pinfunction "QH#_9") (pintype "unspecified"))
      (node (ref "IC-F2") (pin "14") (pinfunction "SI_14") (pintype "unspecified"))
    )
    (net (code "21") (name "Data E-F3") (class "Default")
      (node (ref "IC-E3") (pin "9") (pinfunction "QH#_9") (pintype "unspecified"))
      (node (ref "IC-F3") (pin "14") (pinfunction "SI_14") (pintype "unspecified"))
    )
    (net (code "22") (name "Data F-G") (class "Default")
      (node (ref "IC-F") (pin "9") (pinfunction "QH#_9") (pintype "unspecified"))
      (node (ref "IC-G") (pin "14") (pinfunction "SI_14") (pintype "unspecified"))
    )
    (net (code "23") (name "Data F-G2") (class "Default")
      (node (ref "IC-F2") (pin "9") (pinfunction "QH#_9") (pintype "unspecified"))
      (node (ref "IC-G2") (pin "14") (pinfunction "SI_14") (pintype "unspecified"))
    )
    (net (code "24") (name "Data F-G3") (class "Default")
      (node (ref "IC-F3") (pin "9") (pinfunction "QH#_9") (pintype "unspecified"))
      (node (ref "IC-G3") (pin "14") (pinfunction "SI_14") (pintype "unspecified"))
    )
    (net (code "25") (name "Data G-H") (class "Default")
      (node (ref "IC-G") (pin "9") (pinfunction "QH#_9") (pintype "unspecified"))
      (node (ref "IC-H") (pin "14") (pinfunction "SI_14") (pintype "unspecified"))
    )
    (net (code "26") (name "Data G-H2") (class "Default")
      (node (ref "IC-G2") (pin "9") (pinfunction "QH#_9") (pintype "unspecified"))
      (node (ref "IC-H2") (pin "14") (pinfunction "SI_14") (pintype "unspecified"))
    )
    (net (code "27") (name "Data G-H3") (class "Default")
      (node (ref "IC-G3") (pin "9") (pinfunction "QH#_9") (pintype "unspecified"))
      (node (ref "IC-H3") (pin "14") (pinfunction "SI_14") (pintype "unspecified"))
    )
    (net (code "28") (name "GND") (class "Default")
      (node (ref "H10A") (pin "1") (pinfunction "1_1") (pintype "unspecified"))
      (node (ref "H10A") (pin "10") (pinfunction "10_10") (pintype "unspecified"))
      (node (ref "H10A") (pin "2") (pinfunction "2_2") (pintype "unspecified"))
      (node (ref "H10A") (pin "3") (pinfunction "3_3") (pintype "unspecified"))
      (node (ref "H10A") (pin "4") (pinfunction "4_4") (pintype "unspecified"))
      (node (ref "H10A") (pin "5") (pinfunction "5_5") (pintype "unspecified"))
      (node (ref "H10A") (pin "6") (pinfunction "6_6") (pintype "unspecified"))
      (node (ref "H10A") (pin "7") (pinfunction "7_7") (pintype "unspecified"))
      (node (ref "H10A") (pin "8") (pinfunction "8_8") (pintype "unspecified"))
      (node (ref "H10A") (pin "9") (pinfunction "9_9") (pintype "unspecified"))
      (node (ref "H11A") (pin "1") (pinfunction "1_1") (pintype "unspecified"))
      (node (ref "H11A") (pin "10") (pinfunction "10_10") (pintype "unspecified"))
      (node (ref "H11A") (pin "2") (pinfunction "2_2") (pintype "unspecified"))
      (node (ref "H11A") (pin "3") (pinfunction "3_3") (pintype "unspecified"))
      (node (ref "H11A") (pin "4") (pinfunction "4_4") (pintype "unspecified"))
      (node (ref "H11A") (pin "5") (pinfunction "5_5") (pintype "unspecified"))
      (node (ref "H11A") (pin "6") (pinfunction "6_6") (pintype "unspecified"))
      (node (ref "H11A") (pin "7") (pinfunction "7_7") (pintype "unspecified"))
      (node (ref "H11A") (pin "8") (pinfunction "8_8") (pintype "unspecified"))
      (node (ref "H11A") (pin "9") (pinfunction "9_9") (pintype "unspecified"))
      (node (ref "H12A") (pin "1") (pinfunction "1_1") (pintype "unspecified"))
      (node (ref "H12A") (pin "10") (pinfunction "10_10") (pintype "unspecified"))
      (node (ref "H12A") (pin "2") (pinfunction "2_2") (pintype "unspecified"))
      (node (ref "H12A") (pin "3") (pinfunction "3_3") (pintype "unspecified"))
      (node (ref "H12A") (pin "4") (pinfunction "4_4") (pintype "unspecified"))
      (node (ref "H12A") (pin "5") (pinfunction "5_5") (pintype "unspecified"))
      (node (ref "H12A") (pin "6") (pinfunction "6_6") (pintype "unspecified"))
      (node (ref "H12A") (pin "7") (pinfunction "7_7") (pintype "unspecified"))
      (node (ref "H12A") (pin "8") (pinfunction "8_8") (pintype "unspecified"))
      (node (ref "H12A") (pin "9") (pinfunction "9_9") (pintype "unspecified"))
      (node (ref "H13A") (pin "1") (pinfunction "1_1") (pintype "unspecified"))
      (node (ref "H13A") (pin "10") (pinfunction "10_10") (pintype "unspecified"))
      (node (ref "H13A") (pin "2") (pinfunction "2_2") (pintype "unspecified"))
      (node (ref "H13A") (pin "3") (pinfunction "3_3") (pintype "unspecified"))
      (node (ref "H13A") (pin "4") (pinfunction "4_4") (pintype "unspecified"))
      (node (ref "H13A") (pin "5") (pinfunction "5_5") (pintype "unspecified"))
      (node (ref "H13A") (pin "6") (pinfunction "6_6") (pintype "unspecified"))
      (node (ref "H13A") (pin "7") (pinfunction "7_7") (pintype "unspecified"))
      (node (ref "H13A") (pin "8") (pinfunction "8_8") (pintype "unspecified"))
      (node (ref "H13A") (pin "9") (pinfunction "9_9") (pintype "unspecified"))
      (node (ref "H14A") (pin "1") (pinfunction "1_1") (pintype "unspecified"))
      (node (ref "H14A") (pin "10") (pinfunction "10_10") (pintype "unspecified"))
      (node (ref "H14A") (pin "2") (pinfunction "2_2") (pintype "unspecified"))
      (node (ref "H14A") (pin "3") (pinfunction "3_3") (pintype "unspecified"))
      (node (ref "H14A") (pin "4") (pinfunction "4_4") (pintype "unspecified"))
      (node (ref "H14A") (pin "5") (pinfunction "5_5") (pintype "unspecified"))
      (node (ref "H14A") (pin "6") (pinfunction "6_6") (pintype "unspecified"))
      (node (ref "H14A") (pin "7") (pinfunction "7_7") (pintype "unspecified"))
      (node (ref "H14A") (pin "8") (pinfunction "8_8") (pintype "unspecified"))
      (node (ref "H14A") (pin "9") (pinfunction "9_9") (pintype "unspecified"))
      (node (ref "H15A") (pin "1") (pinfunction "1_1") (pintype "unspecified"))
      (node (ref "H15A") (pin "10") (pinfunction "10_10") (pintype "unspecified"))
      (node (ref "H15A") (pin "2") (pinfunction "2_2") (pintype "unspecified"))
      (node (ref "H15A") (pin "3") (pinfunction "3_3") (pintype "unspecified"))
      (node (ref "H15A") (pin "4") (pinfunction "4_4") (pintype "unspecified"))
      (node (ref "H15A") (pin "5") (pinfunction "5_5") (pintype "unspecified"))
      (node (ref "H15A") (pin "6") (pinfunction "6_6") (pintype "unspecified"))
      (node (ref "H15A") (pin "7") (pinfunction "7_7") (pintype "unspecified"))
      (node (ref "H15A") (pin "8") (pinfunction "8_8") (pintype "unspecified"))
      (node (ref "H15A") (pin "9") (pinfunction "9_9") (pintype "unspecified"))
      (node (ref "H16A") (pin "1") (pinfunction "1_1") (pintype "unspecified"))
      (node (ref "H16A") (pin "10") (pinfunction "10_10") (pintype "unspecified"))
      (node (ref "H16A") (pin "2") (pinfunction "2_2") (pintype "unspecified"))
      (node (ref "H16A") (pin "3") (pinfunction "3_3") (pintype "unspecified"))
      (node (ref "H16A") (pin "4") (pinfunction "4_4") (pintype "unspecified"))
      (node (ref "H16A") (pin "5") (pinfunction "5_5") (pintype "unspecified"))
      (node (ref "H16A") (pin "6") (pinfunction "6_6") (pintype "unspecified"))
      (node (ref "H16A") (pin "7") (pinfunction "7_7") (pintype "unspecified"))
      (node (ref "H16A") (pin "8") (pinfunction "8_8") (pintype "unspecified"))
      (node (ref "H16A") (pin "9") (pinfunction "9_9") (pintype "unspecified"))
      (node (ref "H17A") (pin "1") (pinfunction "1_1") (pintype "unspecified"))
      (node (ref "H17A") (pin "10") (pinfunction "10_10") (pintype "unspecified"))
      (node (ref "H17A") (pin "2") (pinfunction "2_2") (pintype "unspecified"))
      (node (ref "H17A") (pin "3") (pinfunction "3_3") (pintype "unspecified"))
      (node (ref "H17A") (pin "4") (pinfunction "4_4") (pintype "unspecified"))
      (node (ref "H17A") (pin "5") (pinfunction "5_5") (pintype "unspecified"))
      (node (ref "H17A") (pin "6") (pinfunction "6_6") (pintype "unspecified"))
      (node (ref "H17A") (pin "7") (pinfunction "7_7") (pintype "unspecified"))
      (node (ref "H17A") (pin "8") (pinfunction "8_8") (pintype "unspecified"))
      (node (ref "H17A") (pin "9") (pinfunction "9_9") (pintype "unspecified"))
      (node (ref "H18A") (pin "1") (pinfunction "1_1") (pintype "unspecified"))
      (node (ref "H18A") (pin "10") (pinfunction "10_10") (pintype "unspecified"))
      (node (ref "H18A") (pin "2") (pinfunction "2_2") (pintype "unspecified"))
      (node (ref "H18A") (pin "3") (pinfunction "3_3") (pintype "unspecified"))
      (node (ref "H18A") (pin "4") (pinfunction "4_4") (pintype "unspecified"))
      (node (ref "H18A") (pin "5") (pinfunction "5_5") (pintype "unspecified"))
      (node (ref "H18A") (pin "6") (pinfunction "6_6") (pintype "unspecified"))
      (node (ref "H18A") (pin "7") (pinfunction "7_7") (pintype "unspecified"))
      (node (ref "H18A") (pin "8") (pinfunction "8_8") (pintype "unspecified"))
      (node (ref "H18A") (pin "9") (pinfunction "9_9") (pintype "unspecified"))
      (node (ref "H1A") (pin "1") (pinfunction "1_1") (pintype "unspecified"))
      (node (ref "H1A") (pin "10") (pinfunction "10_10") (pintype "unspecified"))
      (node (ref "H1A") (pin "2") (pinfunction "2_2") (pintype "unspecified"))
      (node (ref "H1A") (pin "3") (pinfunction "3_3") (pintype "unspecified"))
      (node (ref "H1A") (pin "4") (pinfunction "4_4") (pintype "unspecified"))
      (node (ref "H1A") (pin "5") (pinfunction "5_5") (pintype "unspecified"))
      (node (ref "H1A") (pin "6") (pinfunction "6_6") (pintype "unspecified"))
      (node (ref "H1A") (pin "7") (pinfunction "7_7") (pintype "unspecified"))
      (node (ref "H1A") (pin "8") (pinfunction "8_8") (pintype "unspecified"))
      (node (ref "H1A") (pin "9") (pinfunction "9_9") (pintype "unspecified"))
      (node (ref "H2A") (pin "1") (pinfunction "1_1") (pintype "unspecified"))
      (node (ref "H2A") (pin "10") (pinfunction "10_10") (pintype "unspecified"))
      (node (ref "H2A") (pin "2") (pinfunction "2_2") (pintype "unspecified"))
      (node (ref "H2A") (pin "3") (pinfunction "3_3") (pintype "unspecified"))
      (node (ref "H2A") (pin "4") (pinfunction "4_4") (pintype "unspecified"))
      (node (ref "H2A") (pin "5") (pinfunction "5_5") (pintype "unspecified"))
      (node (ref "H2A") (pin "6") (pinfunction "6_6") (pintype "unspecified"))
      (node (ref "H2A") (pin "7") (pinfunction "7_7") (pintype "unspecified"))
      (node (ref "H2A") (pin "8") (pinfunction "8_8") (pintype "unspecified"))
      (node (ref "H2A") (pin "9") (pinfunction "9_9") (pintype "unspecified"))
      (node (ref "H3A") (pin "1") (pinfunction "1_1") (pintype "unspecified"))
      (node (ref "H3A") (pin "10") (pinfunction "10_10") (pintype "unspecified"))
      (node (ref "H3A") (pin "2") (pinfunction "2_2") (pintype "unspecified"))
      (node (ref "H3A") (pin "3") (pinfunction "3_3") (pintype "unspecified"))
      (node (ref "H3A") (pin "4") (pinfunction "4_4") (pintype "unspecified"))
      (node (ref "H3A") (pin "5") (pinfunction "5_5") (pintype "unspecified"))
      (node (ref "H3A") (pin "6") (pinfunction "6_6") (pintype "unspecified"))
      (node (ref "H3A") (pin "7") (pinfunction "7_7") (pintype "unspecified"))
      (node (ref "H3A") (pin "8") (pinfunction "8_8") (pintype "unspecified"))
      (node (ref "H3A") (pin "9") (pinfunction "9_9") (pintype "unspecified"))
      (node (ref "H4A") (pin "1") (pinfunction "1_1") (pintype "unspecified"))
      (node (ref "H4A") (pin "10") (pinfunction "10_10") (pintype "unspecified"))
      (node (ref "H4A") (pin "2") (pinfunction "2_2") (pintype "unspecified"))
      (node (ref "H4A") (pin "3") (pinfunction "3_3") (pintype "unspecified"))
      (node (ref "H4A") (pin "4") (pinfunction "4_4") (pintype "unspecified"))
      (node (ref "H4A") (pin "5") (pinfunction "5_5") (pintype "unspecified"))
      (node (ref "H4A") (pin "6") (pinfunction "6_6") (pintype "unspecified"))
      (node (ref "H4A") (pin "7") (pinfunction "7_7") (pintype "unspecified"))
      (node (ref "H4A") (pin "8") (pinfunction "8_8") (pintype "unspecified"))
      (node (ref "H4A") (pin "9") (pinfunction "9_9") (pintype "unspecified"))
      (node (ref "H5A") (pin "1") (pinfunction "1_1") (pintype "unspecified"))
      (node (ref "H5A") (pin "10") (pinfunction "10_10") (pintype "unspecified"))
      (node (ref "H5A") (pin "2") (pinfunction "2_2") (pintype "unspecified"))
      (node (ref "H5A") (pin "3") (pinfunction "3_3") (pintype "unspecified"))
      (node (ref "H5A") (pin "4") (pinfunction "4_4") (pintype "unspecified"))
      (node (ref "H5A") (pin "5") (pinfunction "5_5") (pintype "unspecified"))
      (node (ref "H5A") (pin "6") (pinfunction "6_6") (pintype "unspecified"))
      (node (ref "H5A") (pin "7") (pinfunction "7_7") (pintype "unspecified"))
      (node (ref "H5A") (pin "8") (pinfunction "8_8") (pintype "unspecified"))
      (node (ref "H5A") (pin "9") (pinfunction "9_9") (pintype "unspecified"))
      (node (ref "H6A") (pin "1") (pinfunction "1_1") (pintype "unspecified"))
      (node (ref "H6A") (pin "10") (pinfunction "10_10") (pintype "unspecified"))
      (node (ref "H6A") (pin "2") (pinfunction "2_2") (pintype "unspecified"))
      (node (ref "H6A") (pin "3") (pinfunction "3_3") (pintype "unspecified"))
      (node (ref "H6A") (pin "4") (pinfunction "4_4") (pintype "unspecified"))
      (node (ref "H6A") (pin "5") (pinfunction "5_5") (pintype "unspecified"))
      (node (ref "H6A") (pin "6") (pinfunction "6_6") (pintype "unspecified"))
      (node (ref "H6A") (pin "7") (pinfunction "7_7") (pintype "unspecified"))
      (node (ref "H6A") (pin "8") (pinfunction "8_8") (pintype "unspecified"))
      (node (ref "H6A") (pin "9") (pinfunction "9_9") (pintype "unspecified"))
      (node (ref "H7A") (pin "1") (pinfunction "1_1") (pintype "unspecified"))
      (node (ref "H7A") (pin "10") (pinfunction "10_10") (pintype "unspecified"))
      (node (ref "H7A") (pin "2") (pinfunction "2_2") (pintype "unspecified"))
      (node (ref "H7A") (pin "3") (pinfunction "3_3") (pintype "unspecified"))
      (node (ref "H7A") (pin "4") (pinfunction "4_4") (pintype "unspecified"))
      (node (ref "H7A") (pin "5") (pinfunction "5_5") (pintype "unspecified"))
      (node (ref "H7A") (pin "6") (pinfunction "6_6") (pintype "unspecified"))
      (node (ref "H7A") (pin "7") (pinfunction "7_7") (pintype "unspecified"))
      (node (ref "H7A") (pin "8") (pinfunction "8_8") (pintype "unspecified"))
      (node (ref "H7A") (pin "9") (pinfunction "9_9") (pintype "unspecified"))
      (node (ref "H8A") (pin "1") (pinfunction "1_1") (pintype "unspecified"))
      (node (ref "H8A") (pin "10") (pinfunction "10_10") (pintype "unspecified"))
      (node (ref "H8A") (pin "2") (pinfunction "2_2") (pintype "unspecified"))
      (node (ref "H8A") (pin "3") (pinfunction "3_3") (pintype "unspecified"))
      (node (ref "H8A") (pin "4") (pinfunction "4_4") (pintype "unspecified"))
      (node (ref "H8A") (pin "5") (pinfunction "5_5") (pintype "unspecified"))
      (node (ref "H8A") (pin "6") (pinfunction "6_6") (pintype "unspecified"))
      (node (ref "H8A") (pin "7") (pinfunction "7_7") (pintype "unspecified"))
      (node (ref "H8A") (pin "8") (pinfunction "8_8") (pintype "unspecified"))
      (node (ref "H8A") (pin "9") (pinfunction "9_9") (pintype "unspecified"))
      (node (ref "H9A") (pin "1") (pinfunction "1_1") (pintype "unspecified"))
      (node (ref "H9A") (pin "10") (pinfunction "10_10") (pintype "unspecified"))
      (node (ref "H9A") (pin "2") (pinfunction "2_2") (pintype "unspecified"))
      (node (ref "H9A") (pin "3") (pinfunction "3_3") (pintype "unspecified"))
      (node (ref "H9A") (pin "4") (pinfunction "4_4") (pintype "unspecified"))
      (node (ref "H9A") (pin "5") (pinfunction "5_5") (pintype "unspecified"))
      (node (ref "H9A") (pin "6") (pinfunction "6_6") (pintype "unspecified"))
      (node (ref "H9A") (pin "7") (pinfunction "7_7") (pintype "unspecified"))
      (node (ref "H9A") (pin "8") (pinfunction "8_8") (pintype "unspecified"))
      (node (ref "H9A") (pin "9") (pinfunction "9_9") (pintype "unspecified"))
      (node (ref "IC-A") (pin "13") (pinfunction "G#_13") (pintype "unspecified"))
      (node (ref "IC-A") (pin "8") (pinfunction "GND_8") (pintype "unspecified"))
      (node (ref "IC-A2") (pin "13") (pinfunction "G#_13") (pintype "unspecified"))
      (node (ref "IC-A2") (pin "8") (pinfunction "GND_8") (pintype "unspecified"))
      (node (ref "IC-A3") (pin "13") (pinfunction "G#_13") (pintype "unspecified"))
      (node (ref "IC-A3") (pin "8") (pinfunction "GND_8") (pintype "unspecified"))
      (node (ref "IC-B") (pin "13") (pinfunction "G#_13") (pintype "unspecified"))
      (node (ref "IC-B") (pin "8") (pinfunction "GND_8") (pintype "unspecified"))
      (node (ref "IC-B2") (pin "13") (pinfunction "G#_13") (pintype "unspecified"))
      (node (ref "IC-B2") (pin "8") (pinfunction "GND_8") (pintype "unspecified"))
      (node (ref "IC-B3") (pin "13") (pinfunction "G#_13") (pintype "unspecified"))
      (node (ref "IC-B3") (pin "8") (pinfunction "GND_8") (pintype "unspecified"))
      (node (ref "IC-C") (pin "13") (pinfunction "G#_13") (pintype "unspecified"))
      (node (ref "IC-C") (pin "8") (pinfunction "GND_8") (pintype "unspecified"))
      (node (ref "IC-C2") (pin "13") (pinfunction "G#_13") (pintype "unspecified"))
      (node (ref "IC-C2") (pin "8") (pinfunction "GND_8") (pintype "unspecified"))
      (node (ref "IC-C3") (pin "13") (pinfunction "G#_13") (pintype "unspecified"))
      (node (ref "IC-C3") (pin "8") (pinfunction "GND_8") (pintype "unspecified"))
      (node (ref "IC-D") (pin "13") (pinfunction "G#_13") (pintype "unspecified"))
      (node (ref "IC-D") (pin "8") (pinfunction "GND_8") (pintype "unspecified"))
      (node (ref "IC-D2") (pin "13") (pinfunction "G#_13") (pintype "unspecified"))
      (node (ref "IC-D2") (pin "8") (pinfunction "GND_8") (pintype "unspecified"))
      (node (ref "IC-D3") (pin "13") (pinfunction "G#_13") (pintype "unspecified"))
      (node (ref "IC-D3") (pin "8") (pinfunction "GND_8") (pintype "unspecified"))
      (node (ref "IC-E") (pin "13") (pinfunction "G#_13") (pintype "unspecified"))
      (node (ref "IC-E") (pin "8") (pinfunction "GND_8") (pintype "unspecified"))
      (node (ref "IC-E2") (pin "13") (pinfunction "G#_13") (pintype "unspecified"))
      (node (ref "IC-E2") (pin "8") (pinfunction "GND_8") (pintype "unspecified"))
      (node (ref "IC-E3") (pin "13") (pinfunction "G#_13") (pintype "unspecified"))
      (node (ref "IC-E3") (pin "8") (pinfunction "GND_8") (pintype "unspecified"))
      (node (ref "IC-F") (pin "13") (pinfunction "G#_13") (pintype "unspecified"))
      (node (ref "IC-F") (pin "8") (pinfunction "GND_8") (pintype "unspecified"))
      (node (ref "IC-F2") (pin "13") (pinfunction "G#_13") (pintype "unspecified"))
      (node (ref "IC-F2") (pin "8") (pinfunction "GND_8") (pintype "unspecified"))
      (node (ref "IC-F3") (pin "13") (pinfunction "G#_13") (pintype "unspecified"))
      (node (ref "IC-F3") (pin "8") (pinfunction "GND_8") (pintype "unspecified"))
      (node (ref "IC-G") (pin "13") (pinfunction "G#_13") (pintype "unspecified"))
      (node (ref "IC-G") (pin "8") (pinfunction "GND_8") (pintype "unspecified"))
      (node (ref "IC-G2") (pin "13") (pinfunction "G#_13") (pintype "unspecified"))
      (node (ref "IC-G2") (pin "8") (pinfunction "GND_8") (pintype "unspecified"))
      (node (ref "IC-G3") (pin "13") (pinfunction "G#_13") (pintype "unspecified"))
      (node (ref "IC-G3") (pin "8") (pinfunction "GND_8") (pintype "unspecified"))
      (node (ref "IC-H") (pin "13") (pinfunction "G#_13") (pintype "unspecified"))
      (node (ref "IC-H") (pin "8") (pinfunction "GND_8") (pintype "unspecified"))
      (node (ref "IC-H2") (pin "13") (pinfunction "G#_13") (pintype "unspecified"))
      (node (ref "IC-H2") (pin "8") (pinfunction "GND_8") (pintype "unspecified"))
      (node (ref "IC-H3") (pin "13") (pinfunction "G#_13") (pintype "unspecified"))
      (node (ref "IC-H3") (pin "8") (pinfunction "GND_8") (pintype "unspecified"))
      (node (ref "J1") (pin "3") (pinfunction "3_3") (pintype "unspecified"))
      (node (ref "J1") (pin "4") (pinfunction "4_4") (pintype "unspecified"))
      (node (ref "J2") (pin "3") (pinfunction "3_3") (pintype "unspecified"))
      (node (ref "J2") (pin "4") (pinfunction "4_4") (pintype "unspecified"))
      (node (ref "J3") (pin "3") (pinfunction "3_3") (pintype "unspecified"))
      (node (ref "J3") (pin "4") (pinfunction "4_4") (pintype "unspecified"))
    )
    (net (code "29") (name "Latch (G)") (class "Default")
      (node (ref "IC-A") (pin "12") (pinfunction "RCK_12") (pintype "unspecified"))
      (node (ref "IC-B") (pin "12") (pinfunction "RCK_12") (pintype "unspecified"))
      (node (ref "IC-C") (pin "12") (pinfunction "RCK_12") (pintype "unspecified"))
      (node (ref "IC-D") (pin "12") (pinfunction "RCK_12") (pintype "unspecified"))
      (node (ref "IC-E") (pin "12") (pinfunction "RCK_12") (pintype "unspecified"))
      (node (ref "IC-F") (pin "12") (pinfunction "RCK_12") (pintype "unspecified"))
      (node (ref "IC-G") (pin "12") (pinfunction "RCK_12") (pintype "unspecified"))
      (node (ref "IC-H") (pin "12") (pinfunction "RCK_12") (pintype "unspecified"))
      (node (ref "J1") (pin "7") (pinfunction "7_7") (pintype "unspecified"))
    )
    (net (code "30") (name "Latch 2 (G)") (class "Default")
      (node (ref "IC-A2") (pin "12") (pinfunction "RCK_12") (pintype "unspecified"))
      (node (ref "IC-B2") (pin "12") (pinfunction "RCK_12") (pintype "unspecified"))
      (node (ref "IC-C2") (pin "12") (pinfunction "RCK_12") (pintype "unspecified"))
      (node (ref "IC-D2") (pin "12") (pinfunction "RCK_12") (pintype "unspecified"))
      (node (ref "IC-E2") (pin "12") (pinfunction "RCK_12") (pintype "unspecified"))
      (node (ref "IC-F2") (pin "12") (pinfunction "RCK_12") (pintype "unspecified"))
      (node (ref "IC-G2") (pin "12") (pinfunction "RCK_12") (pintype "unspecified"))
      (node (ref "IC-H2") (pin "12") (pinfunction "RCK_12") (pintype "unspecified"))
      (node (ref "J2") (pin "7") (pinfunction "7_7") (pintype "unspecified"))
    )
    (net (code "31") (name "Latch 3 (G)") (class "Default")
      (node (ref "IC-A3") (pin "12") (pinfunction "RCK_12") (pintype "unspecified"))
      (node (ref "IC-B3") (pin "12") (pinfunction "RCK_12") (pintype "unspecified"))
      (node (ref "IC-C3") (pin "12") (pinfunction "RCK_12") (pintype "unspecified"))
      (node (ref "IC-D3") (pin "12") (pinfunction "RCK_12") (pintype "unspecified"))
      (node (ref "IC-E3") (pin "12") (pinfunction "RCK_12") (pintype "unspecified"))
      (node (ref "IC-F3") (pin "12") (pinfunction "RCK_12") (pintype "unspecified"))
      (node (ref "IC-G3") (pin "12") (pinfunction "RCK_12") (pintype "unspecified"))
      (node (ref "IC-H3") (pin "12") (pinfunction "RCK_12") (pintype "unspecified"))
      (node (ref "J3") (pin "7") (pinfunction "7_7") (pintype "unspecified"))
    )
    (net (code "32") (name "Net-(H1B-Pad1)") (class "Default")
      (node (ref "H1B") (pin "1") (pinfunction "1_1") (pintype "unspecified"))
      (node (ref "R10") (pin "1") (pinfunction "1_1") (pintype "unspecified"))
    )
    (net (code "33") (name "Net-(H1B-Pad2)") (class "Default")
      (node (ref "H1B") (pin "2") (pinfunction "2_2") (pintype "unspecified"))
      (node (ref "R9") (pin "1") (pinfunction "1_1") (pintype "unspecified"))
    )
    (net (code "34") (name "Net-(H1B-Pad3)") (class "Default")
      (node (ref "H1B") (pin "3") (pinfunction "3_3") (pintype "unspecified"))
      (node (ref "R8") (pin "1") (pinfunction "1_1") (pintype "unspecified"))
    )
    (net (code "35") (name "Net-(H1B-Pad4)") (class "Default")
      (node (ref "H1B") (pin "4") (pinfunction "4_4") (pintype "unspecified"))
      (node (ref "R7") (pin "1") (pinfunction "1_1") (pintype "unspecified"))
    )
    (net (code "36") (name "Net-(H1B-Pad5)") (class "Default")
      (node (ref "H1B") (pin "5") (pinfunction "5_5") (pintype "unspecified"))
      (node (ref "R6") (pin "1") (pinfunction "1_1") (pintype "unspecified"))
    )
    (net (code "37") (name "Net-(H1B-Pad6)") (class "Default")
      (node (ref "H1B") (pin "6") (pinfunction "6_6") (pintype "unspecified"))
      (node (ref "R5") (pin "1") (pinfunction "1_1") (pintype "unspecified"))
    )
    (net (code "38") (name "Net-(H1B-Pad7)") (class "Default")
      (node (ref "H1B") (pin "7") (pinfunction "7_7") (pintype "unspecified"))
      (node (ref "R4") (pin "1") (pinfunction "1_1") (pintype "unspecified"))
    )
    (net (code "39") (name "Net-(H1B-Pad8)") (class "Default")
      (node (ref "H1B") (pin "8") (pinfunction "8_8") (pintype "unspecified"))
      (node (ref "R3") (pin "1") (pinfunction "1_1") (pintype "unspecified"))
    )
    (net (code "40") (name "Net-(H1B-Pad9)") (class "Default")
      (node (ref "H1B") (pin "9") (pinfunction "9_9") (pintype "unspecified"))
      (node (ref "R2") (pin "1") (pinfunction "1_1") (pintype "unspecified"))
    )
    (net (code "41") (name "Net-(H1B-Pad10)") (class "Default")
      (node (ref "H1B") (pin "10") (pinfunction "10_10") (pintype "unspecified"))
      (node (ref "R1") (pin "1") (pinfunction "1_1") (pintype "unspecified"))
    )
    (net (code "42") (name "Net-(H2B-Pad1)") (class "Default")
      (node (ref "H2B") (pin "1") (pinfunction "1_1") (pintype "unspecified"))
      (node (ref "R20") (pin "1") (pinfunction "1_1") (pintype "unspecified"))
    )
    (net (code "43") (name "Net-(H2B-Pad2)") (class "Default")
      (node (ref "H2B") (pin "2") (pinfunction "2_2") (pintype "unspecified"))
      (node (ref "R19") (pin "1") (pinfunction "1_1") (pintype "unspecified"))
    )
    (net (code "44") (name "Net-(H2B-Pad3)") (class "Default")
      (node (ref "H2B") (pin "3") (pinfunction "3_3") (pintype "unspecified"))
      (node (ref "R18") (pin "1") (pinfunction "1_1") (pintype "unspecified"))
    )
    (net (code "45") (name "Net-(H2B-Pad4)") (class "Default")
      (node (ref "H2B") (pin "4") (pinfunction "4_4") (pintype "unspecified"))
      (node (ref "R17") (pin "1") (pinfunction "1_1") (pintype "unspecified"))
    )
    (net (code "46") (name "Net-(H2B-Pad5)") (class "Default")
      (node (ref "H2B") (pin "5") (pinfunction "5_5") (pintype "unspecified"))
      (node (ref "R16") (pin "1") (pinfunction "1_1") (pintype "unspecified"))
    )
    (net (code "47") (name "Net-(H2B-Pad6)") (class "Default")
      (node (ref "H2B") (pin "6") (pinfunction "6_6") (pintype "unspecified"))
      (node (ref "R15") (pin "1") (pinfunction "1_1") (pintype "unspecified"))
    )
    (net (code "48") (name "Net-(H2B-Pad7)") (class "Default")
      (node (ref "H2B") (pin "7") (pinfunction "7_7") (pintype "unspecified"))
      (node (ref "R14") (pin "1") (pinfunction "1_1") (pintype "unspecified"))
    )
    (net (code "49") (name "Net-(H2B-Pad8)") (class "Default")
      (node (ref "H2B") (pin "8") (pinfunction "8_8") (pintype "unspecified"))
      (node (ref "R13") (pin "1") (pinfunction "1_1") (pintype "unspecified"))
    )
    (net (code "50") (name "Net-(H2B-Pad9)") (class "Default")
      (node (ref "H2B") (pin "9") (pinfunction "9_9") (pintype "unspecified"))
      (node (ref "R12") (pin "1") (pinfunction "1_1") (pintype "unspecified"))
    )
    (net (code "51") (name "Net-(H2B-Pad10)") (class "Default")
      (node (ref "H2B") (pin "10") (pinfunction "10_10") (pintype "unspecified"))
      (node (ref "R11") (pin "1") (pinfunction "1_1") (pintype "unspecified"))
    )
    (net (code "52") (name "Net-(H3B-Pad1)") (class "Default")
      (node (ref "H3B") (pin "1") (pinfunction "1_1") (pintype "unspecified"))
      (node (ref "R30") (pin "1") (pinfunction "1_1") (pintype "unspecified"))
    )
    (net (code "53") (name "Net-(H3B-Pad2)") (class "Default")
      (node (ref "H3B") (pin "2") (pinfunction "2_2") (pintype "unspecified"))
      (node (ref "R29") (pin "1") (pinfunction "1_1") (pintype "unspecified"))
    )
    (net (code "54") (name "Net-(H3B-Pad3)") (class "Default")
      (node (ref "H3B") (pin "3") (pinfunction "3_3") (pintype "unspecified"))
      (node (ref "R28") (pin "1") (pinfunction "1_1") (pintype "unspecified"))
    )
    (net (code "55") (name "Net-(H3B-Pad4)") (class "Default")
      (node (ref "H3B") (pin "4") (pinfunction "4_4") (pintype "unspecified"))
      (node (ref "R27") (pin "1") (pinfunction "1_1") (pintype "unspecified"))
    )
    (net (code "56") (name "Net-(H3B-Pad5)") (class "Default")
      (node (ref "H3B") (pin "5") (pinfunction "5_5") (pintype "unspecified"))
      (node (ref "R26") (pin "1") (pinfunction "1_1") (pintype "unspecified"))
    )
    (net (code "57") (name "Net-(H3B-Pad6)") (class "Default")
      (node (ref "H3B") (pin "6") (pinfunction "6_6") (pintype "unspecified"))
      (node (ref "R25") (pin "1") (pinfunction "1_1") (pintype "unspecified"))
    )
    (net (code "58") (name "Net-(H3B-Pad7)") (class "Default")
      (node (ref "H3B") (pin "7") (pinfunction "7_7") (pintype "unspecified"))
      (node (ref "R24") (pin "1") (pinfunction "1_1") (pintype "unspecified"))
    )
    (net (code "59") (name "Net-(H3B-Pad8)") (class "Default")
      (node (ref "H3B") (pin "8") (pinfunction "8_8") (pintype "unspecified"))
      (node (ref "R23") (pin "1") (pinfunction "1_1") (pintype "unspecified"))
    )
    (net (code "60") (name "Net-(H3B-Pad9)") (class "Default")
      (node (ref "H3B") (pin "9") (pinfunction "9_9") (pintype "unspecified"))
      (node (ref "R22") (pin "1") (pinfunction "1_1") (pintype "unspecified"))
    )
    (net (code "61") (name "Net-(H3B-Pad10)") (class "Default")
      (node (ref "H3B") (pin "10") (pinfunction "10_10") (pintype "unspecified"))
      (node (ref "R21") (pin "1") (pinfunction "1_1") (pintype "unspecified"))
    )
    (net (code "62") (name "Net-(H4B-Pad1)") (class "Default")
      (node (ref "H4B") (pin "1") (pinfunction "1_1") (pintype "unspecified"))
      (node (ref "R40") (pin "1") (pinfunction "1_1") (pintype "unspecified"))
    )
    (net (code "63") (name "Net-(H4B-Pad2)") (class "Default")
      (node (ref "H4B") (pin "2") (pinfunction "2_2") (pintype "unspecified"))
      (node (ref "R39") (pin "1") (pinfunction "1_1") (pintype "unspecified"))
    )
    (net (code "64") (name "Net-(H4B-Pad3)") (class "Default")
      (node (ref "H4B") (pin "3") (pinfunction "3_3") (pintype "unspecified"))
      (node (ref "R38") (pin "1") (pinfunction "1_1") (pintype "unspecified"))
    )
    (net (code "65") (name "Net-(H4B-Pad4)") (class "Default")
      (node (ref "H4B") (pin "4") (pinfunction "4_4") (pintype "unspecified"))
      (node (ref "R37") (pin "1") (pinfunction "1_1") (pintype "unspecified"))
    )
    (net (code "66") (name "Net-(H4B-Pad5)") (class "Default")
      (node (ref "H4B") (pin "5") (pinfunction "5_5") (pintype "unspecified"))
      (node (ref "R36") (pin "1") (pinfunction "1_1") (pintype "unspecified"))
    )
    (net (code "67") (name "Net-(H4B-Pad6)") (class "Default")
      (node (ref "H4B") (pin "6") (pinfunction "6_6") (pintype "unspecified"))
      (node (ref "R35") (pin "1") (pinfunction "1_1") (pintype "unspecified"))
    )
    (net (code "68") (name "Net-(H4B-Pad7)") (class "Default")
      (node (ref "H4B") (pin "7") (pinfunction "7_7") (pintype "unspecified"))
      (node (ref "R34") (pin "1") (pinfunction "1_1") (pintype "unspecified"))
    )
    (net (code "69") (name "Net-(H4B-Pad8)") (class "Default")
      (node (ref "H4B") (pin "8") (pinfunction "8_8") (pintype "unspecified"))
      (node (ref "R33") (pin "1") (pinfunction "1_1") (pintype "unspecified"))
    )
    (net (code "70") (name "Net-(H4B-Pad9)") (class "Default")
      (node (ref "H4B") (pin "9") (pinfunction "9_9") (pintype "unspecified"))
      (node (ref "R32") (pin "1") (pinfunction "1_1") (pintype "unspecified"))
    )
    (net (code "71") (name "Net-(H4B-Pad10)") (class "Default")
      (node (ref "H4B") (pin "10") (pinfunction "10_10") (pintype "unspecified"))
      (node (ref "R31") (pin "1") (pinfunction "1_1") (pintype "unspecified"))
    )
    (net (code "72") (name "Net-(H5B-Pad1)") (class "Default")
      (node (ref "H5B") (pin "1") (pinfunction "1_1") (pintype "unspecified"))
      (node (ref "R50") (pin "1") (pinfunction "1_1") (pintype "unspecified"))
    )
    (net (code "73") (name "Net-(H5B-Pad2)") (class "Default")
      (node (ref "H5B") (pin "2") (pinfunction "2_2") (pintype "unspecified"))
      (node (ref "R49") (pin "1") (pinfunction "1_1") (pintype "unspecified"))
    )
    (net (code "74") (name "Net-(H5B-Pad3)") (class "Default")
      (node (ref "H5B") (pin "3") (pinfunction "3_3") (pintype "unspecified"))
      (node (ref "R48") (pin "1") (pinfunction "1_1") (pintype "unspecified"))
    )
    (net (code "75") (name "Net-(H5B-Pad4)") (class "Default")
      (node (ref "H5B") (pin "4") (pinfunction "4_4") (pintype "unspecified"))
      (node (ref "R47") (pin "1") (pinfunction "1_1") (pintype "unspecified"))
    )
    (net (code "76") (name "Net-(H5B-Pad5)") (class "Default")
      (node (ref "H5B") (pin "5") (pinfunction "5_5") (pintype "unspecified"))
      (node (ref "R46") (pin "1") (pinfunction "1_1") (pintype "unspecified"))
    )
    (net (code "77") (name "Net-(H5B-Pad6)") (class "Default")
      (node (ref "H5B") (pin "6") (pinfunction "6_6") (pintype "unspecified"))
      (node (ref "R45") (pin "1") (pinfunction "1_1") (pintype "unspecified"))
    )
    (net (code "78") (name "Net-(H5B-Pad7)") (class "Default")
      (node (ref "H5B") (pin "7") (pinfunction "7_7") (pintype "unspecified"))
      (node (ref "R44") (pin "1") (pinfunction "1_1") (pintype "unspecified"))
    )
    (net (code "79") (name "Net-(H5B-Pad8)") (class "Default")
      (node (ref "H5B") (pin "8") (pinfunction "8_8") (pintype "unspecified"))
      (node (ref "R43") (pin "1") (pinfunction "1_1") (pintype "unspecified"))
    )
    (net (code "80") (name "Net-(H5B-Pad9)") (class "Default")
      (node (ref "H5B") (pin "9") (pinfunction "9_9") (pintype "unspecified"))
      (node (ref "R42") (pin "1") (pinfunction "1_1") (pintype "unspecified"))
    )
    (net (code "81") (name "Net-(H5B-Pad10)") (class "Default")
      (node (ref "H5B") (pin "10") (pinfunction "10_10") (pintype "unspecified"))
      (node (ref "R41") (pin "1") (pinfunction "1_1") (pintype "unspecified"))
    )
    (net (code "82") (name "Net-(H6B-Pad1)") (class "Default")
      (node (ref "H6B") (pin "1") (pinfunction "1_1") (pintype "unspecified"))
      (node (ref "R60") (pin "1") (pinfunction "1_1") (pintype "unspecified"))
    )
    (net (code "83") (name "Net-(H6B-Pad2)") (class "Default")
      (node (ref "H6B") (pin "2") (pinfunction "2_2") (pintype "unspecified"))
      (node (ref "R59") (pin "1") (pinfunction "1_1") (pintype "unspecified"))
    )
    (net (code "84") (name "Net-(H6B-Pad3)") (class "Default")
      (node (ref "H6B") (pin "3") (pinfunction "3_3") (pintype "unspecified"))
      (node (ref "R58") (pin "1") (pinfunction "1_1") (pintype "unspecified"))
    )
    (net (code "85") (name "Net-(H6B-Pad4)") (class "Default")
      (node (ref "H6B") (pin "4") (pinfunction "4_4") (pintype "unspecified"))
      (node (ref "R57") (pin "1") (pinfunction "1_1") (pintype "unspecified"))
    )
    (net (code "86") (name "Net-(H6B-Pad5)") (class "Default")
      (node (ref "H6B") (pin "5") (pinfunction "5_5") (pintype "unspecified"))
      (node (ref "R56") (pin "1") (pinfunction "1_1") (pintype "unspecified"))
    )
    (net (code "87") (name "Net-(H6B-Pad6)") (class "Default")
      (node (ref "H6B") (pin "6") (pinfunction "6_6") (pintype "unspecified"))
      (node (ref "R55") (pin "1") (pinfunction "1_1") (pintype "unspecified"))
    )
    (net (code "88") (name "Net-(H6B-Pad7)") (class "Default")
      (node (ref "H6B") (pin "7") (pinfunction "7_7") (pintype "unspecified"))
      (node (ref "R54") (pin "1") (pinfunction "1_1") (pintype "unspecified"))
    )
    (net (code "89") (name "Net-(H6B-Pad8)") (class "Default")
      (node (ref "H6B") (pin "8") (pinfunction "8_8") (pintype "unspecified"))
      (node (ref "R53") (pin "1") (pinfunction "1_1") (pintype "unspecified"))
    )
    (net (code "90") (name "Net-(H6B-Pad9)") (class "Default")
      (node (ref "H6B") (pin "9") (pinfunction "9_9") (pintype "unspecified"))
      (node (ref "R52") (pin "1") (pinfunction "1_1") (pintype "unspecified"))
    )
    (net (code "91") (name "Net-(H6B-Pad10)") (class "Default")
      (node (ref "H6B") (pin "10") (pinfunction "10_10") (pintype "unspecified"))
      (node (ref "R51") (pin "1") (pinfunction "1_1") (pintype "unspecified"))
    )
    (net (code "92") (name "Net-(H7B-Pad1)") (class "Default")
      (node (ref "H7B") (pin "1") (pinfunction "1_1") (pintype "unspecified"))
      (node (ref "R111") (pin "1") (pinfunction "1_1") (pintype "unspecified"))
    )
    (net (code "93") (name "Net-(H7B-Pad2)") (class "Default")
      (node (ref "H7B") (pin "2") (pinfunction "2_2") (pintype "unspecified"))
      (node (ref "R112") (pin "1") (pinfunction "1_1") (pintype "unspecified"))
    )
    (net (code "94") (name "Net-(H7B-Pad3)") (class "Default")
      (node (ref "H7B") (pin "3") (pinfunction "3_3") (pintype "unspecified"))
      (node (ref "R113") (pin "1") (pinfunction "1_1") (pintype "unspecified"))
    )
    (net (code "95") (name "Net-(H7B-Pad4)") (class "Default")
      (node (ref "H7B") (pin "4") (pinfunction "4_4") (pintype "unspecified"))
      (node (ref "R114") (pin "1") (pinfunction "1_1") (pintype "unspecified"))
    )
    (net (code "96") (name "Net-(H7B-Pad5)") (class "Default")
      (node (ref "H7B") (pin "5") (pinfunction "5_5") (pintype "unspecified"))
      (node (ref "R115") (pin "1") (pinfunction "1_1") (pintype "unspecified"))
    )
    (net (code "97") (name "Net-(H7B-Pad6)") (class "Default")
      (node (ref "H7B") (pin "6") (pinfunction "6_6") (pintype "unspecified"))
      (node (ref "R116") (pin "1") (pinfunction "1_1") (pintype "unspecified"))
    )
    (net (code "98") (name "Net-(H7B-Pad7)") (class "Default")
      (node (ref "H7B") (pin "7") (pinfunction "7_7") (pintype "unspecified"))
      (node (ref "R117") (pin "1") (pinfunction "1_1") (pintype "unspecified"))
    )
    (net (code "99") (name "Net-(H7B-Pad8)") (class "Default")
      (node (ref "H7B") (pin "8") (pinfunction "8_8") (pintype "unspecified"))
      (node (ref "R118") (pin "1") (pinfunction "1_1") (pintype "unspecified"))
    )
    (net (code "100") (name "Net-(H7B-Pad9)") (class "Default")
      (node (ref "H7B") (pin "9") (pinfunction "9_9") (pintype "unspecified"))
      (node (ref "R119") (pin "1") (pinfunction "1_1") (pintype "unspecified"))
    )
    (net (code "101") (name "Net-(H7B-Pad10)") (class "Default")
      (node (ref "H7B") (pin "10") (pinfunction "10_10") (pintype "unspecified"))
      (node (ref "R120") (pin "1") (pinfunction "1_1") (pintype "unspecified"))
    )
    (net (code "102") (name "Net-(H8B-Pad1)") (class "Default")
      (node (ref "H8B") (pin "1") (pinfunction "1_1") (pintype "unspecified"))
      (node (ref "R101") (pin "1") (pinfunction "1_1") (pintype "unspecified"))
    )
    (net (code "103") (name "Net-(H8B-Pad2)") (class "Default")
      (node (ref "H8B") (pin "2") (pinfunction "2_2") (pintype "unspecified"))
      (node (ref "R102") (pin "1") (pinfunction "1_1") (pintype "unspecified"))
    )
    (net (code "104") (name "Net-(H8B-Pad3)") (class "Default")
      (node (ref "H8B") (pin "3") (pinfunction "3_3") (pintype "unspecified"))
      (node (ref "R103") (pin "1") (pinfunction "1_1") (pintype "unspecified"))
    )
    (net (code "105") (name "Net-(H8B-Pad4)") (class "Default")
      (node (ref "H8B") (pin "4") (pinfunction "4_4") (pintype "unspecified"))
      (node (ref "R104") (pin "1") (pinfunction "1_1") (pintype "unspecified"))
    )
    (net (code "106") (name "Net-(H8B-Pad5)") (class "Default")
      (node (ref "H8B") (pin "5") (pinfunction "5_5") (pintype "unspecified"))
      (node (ref "R105") (pin "1") (pinfunction "1_1") (pintype "unspecified"))
    )
    (net (code "107") (name "Net-(H8B-Pad6)") (class "Default")
      (node (ref "H8B") (pin "6") (pinfunction "6_6") (pintype "unspecified"))
      (node (ref "R106") (pin "1") (pinfunction "1_1") (pintype "unspecified"))
    )
    (net (code "108") (name "Net-(H8B-Pad7)") (class "Default")
      (node (ref "H8B") (pin "7") (pinfunction "7_7") (pintype "unspecified"))
      (node (ref "R107") (pin "1") (pinfunction "1_1") (pintype "unspecified"))
    )
    (net (code "109") (name "Net-(H8B-Pad8)") (class "Default")
      (node (ref "H8B") (pin "8") (pinfunction "8_8") (pintype "unspecified"))
      (node (ref "R108") (pin "1") (pinfunction "1_1") (pintype "unspecified"))
    )
    (net (code "110") (name "Net-(H8B-Pad9)") (class "Default")
      (node (ref "H8B") (pin "9") (pinfunction "9_9") (pintype "unspecified"))
      (node (ref "R109") (pin "1") (pinfunction "1_1") (pintype "unspecified"))
    )
    (net (code "111") (name "Net-(H8B-Pad10)") (class "Default")
      (node (ref "H8B") (pin "10") (pinfunction "10_10") (pintype "unspecified"))
      (node (ref "R110") (pin "1") (pinfunction "1_1") (pintype "unspecified"))
    )
    (net (code "112") (name "Net-(H9B-Pad1)") (class "Default")
      (node (ref "H9B") (pin "1") (pinfunction "1_1") (pintype "unspecified"))
      (node (ref "R91") (pin "1") (pinfunction "1_1") (pintype "unspecified"))
    )
    (net (code "113") (name "Net-(H9B-Pad2)") (class "Default")
      (node (ref "H9B") (pin "2") (pinfunction "2_2") (pintype "unspecified"))
      (node (ref "R92") (pin "1") (pinfunction "1_1") (pintype "unspecified"))
    )
    (net (code "114") (name "Net-(H9B-Pad3)") (class "Default")
      (node (ref "H9B") (pin "3") (pinfunction "3_3") (pintype "unspecified"))
      (node (ref "R93") (pin "1") (pinfunction "1_1") (pintype "unspecified"))
    )
    (net (code "115") (name "Net-(H9B-Pad4)") (class "Default")
      (node (ref "H9B") (pin "4") (pinfunction "4_4") (pintype "unspecified"))
      (node (ref "R94") (pin "1") (pinfunction "1_1") (pintype "unspecified"))
    )
    (net (code "116") (name "Net-(H9B-Pad5)") (class "Default")
      (node (ref "H9B") (pin "5") (pinfunction "5_5") (pintype "unspecified"))
      (node (ref "R95") (pin "1") (pinfunction "1_1") (pintype "unspecified"))
    )
    (net (code "117") (name "Net-(H9B-Pad6)") (class "Default")
      (node (ref "H9B") (pin "6") (pinfunction "6_6") (pintype "unspecified"))
      (node (ref "R96") (pin "1") (pinfunction "1_1") (pintype "unspecified"))
    )
    (net (code "118") (name "Net-(H9B-Pad7)") (class "Default")
      (node (ref "H9B") (pin "7") (pinfunction "7_7") (pintype "unspecified"))
      (node (ref "R97") (pin "1") (pinfunction "1_1") (pintype "unspecified"))
    )
    (net (code "119") (name "Net-(H9B-Pad8)") (class "Default")
      (node (ref "H9B") (pin "8") (pinfunction "8_8") (pintype "unspecified"))
      (node (ref "R98") (pin "1") (pinfunction "1_1") (pintype "unspecified"))
    )
    (net (code "120") (name "Net-(H9B-Pad9)") (class "Default")
      (node (ref "H9B") (pin "9") (pinfunction "9_9") (pintype "unspecified"))
      (node (ref "R99") (pin "1") (pinfunction "1_1") (pintype "unspecified"))
    )
    (net (code "121") (name "Net-(H9B-Pad10)") (class "Default")
      (node (ref "H9B") (pin "10") (pinfunction "10_10") (pintype "unspecified"))
      (node (ref "R100") (pin "1") (pinfunction "1_1") (pintype "unspecified"))
    )
    (net (code "122") (name "Net-(H10B-Pad1)") (class "Default")
      (node (ref "H10B") (pin "1") (pinfunction "1_1") (pintype "unspecified"))
      (node (ref "R81") (pin "1") (pinfunction "1_1") (pintype "unspecified"))
    )
    (net (code "123") (name "Net-(H10B-Pad2)") (class "Default")
      (node (ref "H10B") (pin "2") (pinfunction "2_2") (pintype "unspecified"))
      (node (ref "R82") (pin "1") (pinfunction "1_1") (pintype "unspecified"))
    )
    (net (code "124") (name "Net-(H10B-Pad3)") (class "Default")
      (node (ref "H10B") (pin "3") (pinfunction "3_3") (pintype "unspecified"))
      (node (ref "R83") (pin "1") (pinfunction "1_1") (pintype "unspecified"))
    )
    (net (code "125") (name "Net-(H10B-Pad4)") (class "Default")
      (node (ref "H10B") (pin "4") (pinfunction "4_4") (pintype "unspecified"))
      (node (ref "R84") (pin "1") (pinfunction "1_1") (pintype "unspecified"))
    )
    (net (code "126") (name "Net-(H10B-Pad5)") (class "Default")
      (node (ref "H10B") (pin "5") (pinfunction "5_5") (pintype "unspecified"))
      (node (ref "R85") (pin "1") (pinfunction "1_1") (pintype "unspecified"))
    )
    (net (code "127") (name "Net-(H10B-Pad6)") (class "Default")
      (node (ref "H10B") (pin "6") (pinfunction "6_6") (pintype "unspecified"))
      (node (ref "R86") (pin "1") (pinfunction "1_1") (pintype "unspecified"))
    )
    (net (code "128") (name "Net-(H10B-Pad7)") (class "Default")
      (node (ref "H10B") (pin "7") (pinfunction "7_7") (pintype "unspecified"))
      (node (ref "R87") (pin "1") (pinfunction "1_1") (pintype "unspecified"))
    )
    (net (code "129") (name "Net-(H10B-Pad8)") (class "Default")
      (node (ref "H10B") (pin "8") (pinfunction "8_8") (pintype "unspecified"))
      (node (ref "R88") (pin "1") (pinfunction "1_1") (pintype "unspecified"))
    )
    (net (code "130") (name "Net-(H10B-Pad9)") (class "Default")
      (node (ref "H10B") (pin "9") (pinfunction "9_9") (pintype "unspecified"))
      (node (ref "R89") (pin "1") (pinfunction "1_1") (pintype "unspecified"))
    )
    (net (code "131") (name "Net-(H10B-Pad10)") (class "Default")
      (node (ref "H10B") (pin "10") (pinfunction "10_10") (pintype "unspecified"))
      (node (ref "R90") (pin "1") (pinfunction "1_1") (pintype "unspecified"))
    )
    (net (code "132") (name "Net-(H11B-Pad1)") (class "Default")
      (node (ref "H11B") (pin "1") (pinfunction "1_1") (pintype "unspecified"))
      (node (ref "R71") (pin "1") (pinfunction "1_1") (pintype "unspecified"))
    )
    (net (code "133") (name "Net-(H11B-Pad2)") (class "Default")
      (node (ref "H11B") (pin "2") (pinfunction "2_2") (pintype "unspecified"))
      (node (ref "R72") (pin "1") (pinfunction "1_1") (pintype "unspecified"))
    )
    (net (code "134") (name "Net-(H11B-Pad3)") (class "Default")
      (node (ref "H11B") (pin "3") (pinfunction "3_3") (pintype "unspecified"))
      (node (ref "R73") (pin "1") (pinfunction "1_1") (pintype "unspecified"))
    )
    (net (code "135") (name "Net-(H11B-Pad4)") (class "Default")
      (node (ref "H11B") (pin "4") (pinfunction "4_4") (pintype "unspecified"))
      (node (ref "R74") (pin "1") (pinfunction "1_1") (pintype "unspecified"))
    )
    (net (code "136") (name "Net-(H11B-Pad5)") (class "Default")
      (node (ref "H11B") (pin "5") (pinfunction "5_5") (pintype "unspecified"))
      (node (ref "R75") (pin "1") (pinfunction "1_1") (pintype "unspecified"))
    )
    (net (code "137") (name "Net-(H11B-Pad6)") (class "Default")
      (node (ref "H11B") (pin "6") (pinfunction "6_6") (pintype "unspecified"))
      (node (ref "R76") (pin "1") (pinfunction "1_1") (pintype "unspecified"))
    )
    (net (code "138") (name "Net-(H11B-Pad7)") (class "Default")
      (node (ref "H11B") (pin "7") (pinfunction "7_7") (pintype "unspecified"))
      (node (ref "R77") (pin "1") (pinfunction "1_1") (pintype "unspecified"))
    )
    (net (code "139") (name "Net-(H11B-Pad8)") (class "Default")
      (node (ref "H11B") (pin "8") (pinfunction "8_8") (pintype "unspecified"))
      (node (ref "R78") (pin "1") (pinfunction "1_1") (pintype "unspecified"))
    )
    (net (code "140") (name "Net-(H11B-Pad9)") (class "Default")
      (node (ref "H11B") (pin "9") (pinfunction "9_9") (pintype "unspecified"))
      (node (ref "R79") (pin "1") (pinfunction "1_1") (pintype "unspecified"))
    )
    (net (code "141") (name "Net-(H11B-Pad10)") (class "Default")
      (node (ref "H11B") (pin "10") (pinfunction "10_10") (pintype "unspecified"))
      (node (ref "R80") (pin "1") (pinfunction "1_1") (pintype "unspecified"))
    )
    (net (code "142") (name "Net-(H12B-Pad1)") (class "Default")
      (node (ref "H12B") (pin "1") (pinfunction "1_1") (pintype "unspecified"))
      (node (ref "R61") (pin "1") (pinfunction "1_1") (pintype "unspecified"))
    )
    (net (code "143") (name "Net-(H12B-Pad2)") (class "Default")
      (node (ref "H12B") (pin "2") (pinfunction "2_2") (pintype "unspecified"))
      (node (ref "R62") (pin "1") (pinfunction "1_1") (pintype "unspecified"))
    )
    (net (code "144") (name "Net-(H12B-Pad3)") (class "Default")
      (node (ref "H12B") (pin "3") (pinfunction "3_3") (pintype "unspecified"))
      (node (ref "R63") (pin "1") (pinfunction "1_1") (pintype "unspecified"))
    )
    (net (code "145") (name "Net-(H12B-Pad4)") (class "Default")
      (node (ref "H12B") (pin "4") (pinfunction "4_4") (pintype "unspecified"))
      (node (ref "R64") (pin "1") (pinfunction "1_1") (pintype "unspecified"))
    )
    (net (code "146") (name "Net-(H12B-Pad5)") (class "Default")
      (node (ref "H12B") (pin "5") (pinfunction "5_5") (pintype "unspecified"))
      (node (ref "R65") (pin "1") (pinfunction "1_1") (pintype "unspecified"))
    )
    (net (code "147") (name "Net-(H12B-Pad6)") (class "Default")
      (node (ref "H12B") (pin "6") (pinfunction "6_6") (pintype "unspecified"))
      (node (ref "R66") (pin "1") (pinfunction "1_1") (pintype "unspecified"))
    )
    (net (code "148") (name "Net-(H12B-Pad7)") (class "Default")
      (node (ref "H12B") (pin "7") (pinfunction "7_7") (pintype "unspecified"))
      (node (ref "R67") (pin "1") (pinfunction "1_1") (pintype "unspecified"))
    )
    (net (code "149") (name "Net-(H12B-Pad8)") (class "Default")
      (node (ref "H12B") (pin "8") (pinfunction "8_8") (pintype "unspecified"))
      (node (ref "R68") (pin "1") (pinfunction "1_1") (pintype "unspecified"))
    )
    (net (code "150") (name "Net-(H12B-Pad9)") (class "Default")
      (node (ref "H12B") (pin "9") (pinfunction "9_9") (pintype "unspecified"))
      (node (ref "R69") (pin "1") (pinfunction "1_1") (pintype "unspecified"))
    )
    (net (code "151") (name "Net-(H12B-Pad10)") (class "Default")
      (node (ref "H12B") (pin "10") (pinfunction "10_10") (pintype "unspecified"))
      (node (ref "R70") (pin "1") (pinfunction "1_1") (pintype "unspecified"))
    )
    (net (code "152") (name "Net-(H13B-Pad1)") (class "Default")
      (node (ref "H13B") (pin "1") (pinfunction "1_1") (pintype "unspecified"))
      (node (ref "R130") (pin "1") (pinfunction "1_1") (pintype "unspecified"))
    )
    (net (code "153") (name "Net-(H13B-Pad2)") (class "Default")
      (node (ref "H13B") (pin "2") (pinfunction "2_2") (pintype "unspecified"))
      (node (ref "R129") (pin "1") (pinfunction "1_1") (pintype "unspecified"))
    )
    (net (code "154") (name "Net-(H13B-Pad3)") (class "Default")
      (node (ref "H13B") (pin "3") (pinfunction "3_3") (pintype "unspecified"))
      (node (ref "R128") (pin "1") (pinfunction "1_1") (pintype "unspecified"))
    )
    (net (code "155") (name "Net-(H13B-Pad4)") (class "Default")
      (node (ref "H13B") (pin "4") (pinfunction "4_4") (pintype "unspecified"))
      (node (ref "R127") (pin "1") (pinfunction "1_1") (pintype "unspecified"))
    )
    (net (code "156") (name "Net-(H13B-Pad5)") (class "Default")
      (node (ref "H13B") (pin "5") (pinfunction "5_5") (pintype "unspecified"))
      (node (ref "R126") (pin "1") (pinfunction "1_1") (pintype "unspecified"))
    )
    (net (code "157") (name "Net-(H13B-Pad6)") (class "Default")
      (node (ref "H13B") (pin "6") (pinfunction "6_6") (pintype "unspecified"))
      (node (ref "R125") (pin "1") (pinfunction "1_1") (pintype "unspecified"))
    )
    (net (code "158") (name "Net-(H13B-Pad7)") (class "Default")
      (node (ref "H13B") (pin "7") (pinfunction "7_7") (pintype "unspecified"))
      (node (ref "R124") (pin "1") (pinfunction "1_1") (pintype "unspecified"))
    )
    (net (code "159") (name "Net-(H13B-Pad8)") (class "Default")
      (node (ref "H13B") (pin "8") (pinfunction "8_8") (pintype "unspecified"))
      (node (ref "R123") (pin "1") (pinfunction "1_1") (pintype "unspecified"))
    )
    (net (code "160") (name "Net-(H13B-Pad9)") (class "Default")
      (node (ref "H13B") (pin "9") (pinfunction "9_9") (pintype "unspecified"))
      (node (ref "R122") (pin "1") (pinfunction "1_1") (pintype "unspecified"))
    )
    (net (code "161") (name "Net-(H13B-Pad10)") (class "Default")
      (node (ref "H13B") (pin "10") (pinfunction "10_10") (pintype "unspecified"))
      (node (ref "R121") (pin "1") (pinfunction "1_1") (pintype "unspecified"))
    )
    (net (code "162") (name "Net-(H14B-Pad1)") (class "Default")
      (node (ref "H14B") (pin "1") (pinfunction "1_1") (pintype "unspecified"))
      (node (ref "R140") (pin "1") (pinfunction "1_1") (pintype "unspecified"))
    )
    (net (code "163") (name "Net-(H14B-Pad2)") (class "Default")
      (node (ref "H14B") (pin "2") (pinfunction "2_2") (pintype "unspecified"))
      (node (ref "R139") (pin "1") (pinfunction "1_1") (pintype "unspecified"))
    )
    (net (code "164") (name "Net-(H14B-Pad3)") (class "Default")
      (node (ref "H14B") (pin "3") (pinfunction "3_3") (pintype "unspecified"))
      (node (ref "R138") (pin "1") (pinfunction "1_1") (pintype "unspecified"))
    )
    (net (code "165") (name "Net-(H14B-Pad4)") (class "Default")
      (node (ref "H14B") (pin "4") (pinfunction "4_4") (pintype "unspecified"))
      (node (ref "R137") (pin "1") (pinfunction "1_1") (pintype "unspecified"))
    )
    (net (code "166") (name "Net-(H14B-Pad5)") (class "Default")
      (node (ref "H14B") (pin "5") (pinfunction "5_5") (pintype "unspecified"))
      (node (ref "R136") (pin "1") (pinfunction "1_1") (pintype "unspecified"))
    )
    (net (code "167") (name "Net-(H14B-Pad6)") (class "Default")
      (node (ref "H14B") (pin "6") (pinfunction "6_6") (pintype "unspecified"))
      (node (ref "R135") (pin "1") (pinfunction "1_1") (pintype "unspecified"))
    )
    (net (code "168") (name "Net-(H14B-Pad7)") (class "Default")
      (node (ref "H14B") (pin "7") (pinfunction "7_7") (pintype "unspecified"))
      (node (ref "R134") (pin "1") (pinfunction "1_1") (pintype "unspecified"))
    )
    (net (code "169") (name "Net-(H14B-Pad8)") (class "Default")
      (node (ref "H14B") (pin "8") (pinfunction "8_8") (pintype "unspecified"))
      (node (ref "R133") (pin "1") (pinfunction "1_1") (pintype "unspecified"))
    )
    (net (code "170") (name "Net-(H14B-Pad9)") (class "Default")
      (node (ref "H14B") (pin "9") (pinfunction "9_9") (pintype "unspecified"))
      (node (ref "R132") (pin "1") (pinfunction "1_1") (pintype "unspecified"))
    )
    (net (code "171") (name "Net-(H14B-Pad10)") (class "Default")
      (node (ref "H14B") (pin "10") (pinfunction "10_10") (pintype "unspecified"))
      (node (ref "R131") (pin "1") (pinfunction "1_1") (pintype "unspecified"))
    )
    (net (code "172") (name "Net-(H15B-Pad1)") (class "Default")
      (node (ref "H15B") (pin "1") (pinfunction "1_1") (pintype "unspecified"))
      (node (ref "R150") (pin "1") (pinfunction "1_1") (pintype "unspecified"))
    )
    (net (code "173") (name "Net-(H15B-Pad2)") (class "Default")
      (node (ref "H15B") (pin "2") (pinfunction "2_2") (pintype "unspecified"))
      (node (ref "R149") (pin "1") (pinfunction "1_1") (pintype "unspecified"))
    )
    (net (code "174") (name "Net-(H15B-Pad3)") (class "Default")
      (node (ref "H15B") (pin "3") (pinfunction "3_3") (pintype "unspecified"))
      (node (ref "R148") (pin "1") (pinfunction "1_1") (pintype "unspecified"))
    )
    (net (code "175") (name "Net-(H15B-Pad4)") (class "Default")
      (node (ref "H15B") (pin "4") (pinfunction "4_4") (pintype "unspecified"))
      (node (ref "R147") (pin "1") (pinfunction "1_1") (pintype "unspecified"))
    )
    (net (code "176") (name "Net-(H15B-Pad5)") (class "Default")
      (node (ref "H15B") (pin "5") (pinfunction "5_5") (pintype "unspecified"))
      (node (ref "R146") (pin "1") (pinfunction "1_1") (pintype "unspecified"))
    )
    (net (code "177") (name "Net-(H15B-Pad6)") (class "Default")
      (node (ref "H15B") (pin "6") (pinfunction "6_6") (pintype "unspecified"))
      (node (ref "R145") (pin "1") (pinfunction "1_1") (pintype "unspecified"))
    )
    (net (code "178") (name "Net-(H15B-Pad7)") (class "Default")
      (node (ref "H15B") (pin "7") (pinfunction "7_7") (pintype "unspecified"))
      (node (ref "R144") (pin "1") (pinfunction "1_1") (pintype "unspecified"))
    )
    (net (code "179") (name "Net-(H15B-Pad8)") (class "Default")
      (node (ref "H15B") (pin "8") (pinfunction "8_8") (pintype "unspecified"))
      (node (ref "R143") (pin "1") (pinfunction "1_1") (pintype "unspecified"))
    )
    (net (code "180") (name "Net-(H15B-Pad9)") (class "Default")
      (node (ref "H15B") (pin "9") (pinfunction "9_9") (pintype "unspecified"))
      (node (ref "R142") (pin "1") (pinfunction "1_1") (pintype "unspecified"))
    )
    (net (code "181") (name "Net-(H15B-Pad10)") (class "Default")
      (node (ref "H15B") (pin "10") (pinfunction "10_10") (pintype "unspecified"))
      (node (ref "R141") (pin "1") (pinfunction "1_1") (pintype "unspecified"))
    )
    (net (code "182") (name "Net-(H16B-Pad1)") (class "Default")
      (node (ref "H16B") (pin "1") (pinfunction "1_1") (pintype "unspecified"))
      (node (ref "R160") (pin "1") (pinfunction "1_1") (pintype "unspecified"))
    )
    (net (code "183") (name "Net-(H16B-Pad2)") (class "Default")
      (node (ref "H16B") (pin "2") (pinfunction "2_2") (pintype "unspecified"))
      (node (ref "R159") (pin "1") (pinfunction "1_1") (pintype "unspecified"))
    )
    (net (code "184") (name "Net-(H16B-Pad3)") (class "Default")
      (node (ref "H16B") (pin "3") (pinfunction "3_3") (pintype "unspecified"))
      (node (ref "R158") (pin "1") (pinfunction "1_1") (pintype "unspecified"))
    )
    (net (code "185") (name "Net-(H16B-Pad4)") (class "Default")
      (node (ref "H16B") (pin "4") (pinfunction "4_4") (pintype "unspecified"))
      (node (ref "R157") (pin "1") (pinfunction "1_1") (pintype "unspecified"))
    )
    (net (code "186") (name "Net-(H16B-Pad5)") (class "Default")
      (node (ref "H16B") (pin "5") (pinfunction "5_5") (pintype "unspecified"))
      (node (ref "R156") (pin "1") (pinfunction "1_1") (pintype "unspecified"))
    )
    (net (code "187") (name "Net-(H16B-Pad6)") (class "Default")
      (node (ref "H16B") (pin "6") (pinfunction "6_6") (pintype "unspecified"))
      (node (ref "R155") (pin "1") (pinfunction "1_1") (pintype "unspecified"))
    )
    (net (code "188") (name "Net-(H16B-Pad7)") (class "Default")
      (node (ref "H16B") (pin "7") (pinfunction "7_7") (pintype "unspecified"))
      (node (ref "R154") (pin "1") (pinfunction "1_1") (pintype "unspecified"))
    )
    (net (code "189") (name "Net-(H16B-Pad8)") (class "Default")
      (node (ref "H16B") (pin "8") (pinfunction "8_8") (pintype "unspecified"))
      (node (ref "R153") (pin "1") (pinfunction "1_1") (pintype "unspecified"))
    )
    (net (code "190") (name "Net-(H16B-Pad9)") (class "Default")
      (node (ref "H16B") (pin "9") (pinfunction "9_9") (pintype "unspecified"))
      (node (ref "R152") (pin "1") (pinfunction "1_1") (pintype "unspecified"))
    )
    (net (code "191") (name "Net-(H16B-Pad10)") (class "Default")
      (node (ref "H16B") (pin "10") (pinfunction "10_10") (pintype "unspecified"))
      (node (ref "R151") (pin "1") (pinfunction "1_1") (pintype "unspecified"))
    )
    (net (code "192") (name "Net-(H17B-Pad1)") (class "Default")
      (node (ref "H17B") (pin "1") (pinfunction "1_1") (pintype "unspecified"))
      (node (ref "R170") (pin "1") (pinfunction "1_1") (pintype "unspecified"))
    )
    (net (code "193") (name "Net-(H17B-Pad2)") (class "Default")
      (node (ref "H17B") (pin "2") (pinfunction "2_2") (pintype "unspecified"))
      (node (ref "R169") (pin "1") (pinfunction "1_1") (pintype "unspecified"))
    )
    (net (code "194") (name "Net-(H17B-Pad3)") (class "Default")
      (node (ref "H17B") (pin "3") (pinfunction "3_3") (pintype "unspecified"))
      (node (ref "R168") (pin "1") (pinfunction "1_1") (pintype "unspecified"))
    )
    (net (code "195") (name "Net-(H17B-Pad4)") (class "Default")
      (node (ref "H17B") (pin "4") (pinfunction "4_4") (pintype "unspecified"))
      (node (ref "R167") (pin "1") (pinfunction "1_1") (pintype "unspecified"))
    )
    (net (code "196") (name "Net-(H17B-Pad5)") (class "Default")
      (node (ref "H17B") (pin "5") (pinfunction "5_5") (pintype "unspecified"))
      (node (ref "R166") (pin "1") (pinfunction "1_1") (pintype "unspecified"))
    )
    (net (code "197") (name "Net-(H17B-Pad6)") (class "Default")
      (node (ref "H17B") (pin "6") (pinfunction "6_6") (pintype "unspecified"))
      (node (ref "R165") (pin "1") (pinfunction "1_1") (pintype "unspecified"))
    )
    (net (code "198") (name "Net-(H17B-Pad7)") (class "Default")
      (node (ref "H17B") (pin "7") (pinfunction "7_7") (pintype "unspecified"))
      (node (ref "R164") (pin "1") (pinfunction "1_1") (pintype "unspecified"))
    )
    (net (code "199") (name "Net-(H17B-Pad8)") (class "Default")
      (node (ref "H17B") (pin "8") (pinfunction "8_8") (pintype "unspecified"))
      (node (ref "R163") (pin "1") (pinfunction "1_1") (pintype "unspecified"))
    )
    (net (code "200") (name "Net-(H17B-Pad9)") (class "Default")
      (node (ref "H17B") (pin "9") (pinfunction "9_9") (pintype "unspecified"))
      (node (ref "R162") (pin "1") (pinfunction "1_1") (pintype "unspecified"))
    )
    (net (code "201") (name "Net-(H17B-Pad10)") (class "Default")
      (node (ref "H17B") (pin "10") (pinfunction "10_10") (pintype "unspecified"))
      (node (ref "R161") (pin "1") (pinfunction "1_1") (pintype "unspecified"))
    )
    (net (code "202") (name "Net-(H18B-Pad1)") (class "Default")
      (node (ref "H18B") (pin "1") (pinfunction "1_1") (pintype "unspecified"))
      (node (ref "R180") (pin "1") (pinfunction "1_1") (pintype "unspecified"))
    )
    (net (code "203") (name "Net-(H18B-Pad2)") (class "Default")
      (node (ref "H18B") (pin "2") (pinfunction "2_2") (pintype "unspecified"))
      (node (ref "R179") (pin "1") (pinfunction "1_1") (pintype "unspecified"))
    )
    (net (code "204") (name "Net-(H18B-Pad3)") (class "Default")
      (node (ref "H18B") (pin "3") (pinfunction "3_3") (pintype "unspecified"))
      (node (ref "R178") (pin "1") (pinfunction "1_1") (pintype "unspecified"))
    )
    (net (code "205") (name "Net-(H18B-Pad4)") (class "Default")
      (node (ref "H18B") (pin "4") (pinfunction "4_4") (pintype "unspecified"))
      (node (ref "R177") (pin "1") (pinfunction "1_1") (pintype "unspecified"))
    )
    (net (code "206") (name "Net-(H18B-Pad5)") (class "Default")
      (node (ref "H18B") (pin "5") (pinfunction "5_5") (pintype "unspecified"))
      (node (ref "R176") (pin "1") (pinfunction "1_1") (pintype "unspecified"))
    )
    (net (code "207") (name "Net-(H18B-Pad6)") (class "Default")
      (node (ref "H18B") (pin "6") (pinfunction "6_6") (pintype "unspecified"))
      (node (ref "R175") (pin "1") (pinfunction "1_1") (pintype "unspecified"))
    )
    (net (code "208") (name "Net-(H18B-Pad7)") (class "Default")
      (node (ref "H18B") (pin "7") (pinfunction "7_7") (pintype "unspecified"))
      (node (ref "R174") (pin "1") (pinfunction "1_1") (pintype "unspecified"))
    )
    (net (code "209") (name "Net-(H18B-Pad8)") (class "Default")
      (node (ref "H18B") (pin "8") (pinfunction "8_8") (pintype "unspecified"))
      (node (ref "R173") (pin "1") (pinfunction "1_1") (pintype "unspecified"))
    )
    (net (code "210") (name "Net-(H18B-Pad9)") (class "Default")
      (node (ref "H18B") (pin "9") (pinfunction "9_9") (pintype "unspecified"))
      (node (ref "R172") (pin "1") (pinfunction "1_1") (pintype "unspecified"))
    )
    (net (code "211") (name "Net-(H18B-Pad10)") (class "Default")
      (node (ref "H18B") (pin "10") (pinfunction "10_10") (pintype "unspecified"))
      (node (ref "R171") (pin "1") (pinfunction "1_1") (pintype "unspecified"))
    )
    (net (code "212") (name "Out 0A") (class "Default")
      (node (ref "IC-A") (pin "15") (pinfunction "QA_15") (pintype "unspecified"))
      (node (ref "R1") (pin "2") (pinfunction "2_2") (pintype "unspecified"))
    )
    (net (code "213") (name "Out 0A2") (class "Default")
      (node (ref "IC-A2") (pin "15") (pinfunction "QA_15") (pintype "unspecified"))
      (node (ref "R120") (pin "2") (pinfunction "2_2") (pintype "unspecified"))
    )
    (net (code "214") (name "Out 0A3") (class "Default")
      (node (ref "IC-A3") (pin "15") (pinfunction "QA_15") (pintype "unspecified"))
      (node (ref "R121") (pin "2") (pinfunction "2_2") (pintype "unspecified"))
    )
    (net (code "215") (name "Out 0B") (class "Default")
      (node (ref "IC-B") (pin "15") (pinfunction "QA_15") (pintype "unspecified"))
      (node (ref "R9") (pin "2") (pinfunction "2_2") (pintype "unspecified"))
    )
    (net (code "216") (name "Out 0B2") (class "Default")
      (node (ref "IC-B2") (pin "15") (pinfunction "QA_15") (pintype "unspecified"))
      (node (ref "R112") (pin "2") (pinfunction "2_2") (pintype "unspecified"))
    )
    (net (code "217") (name "Out 0B3") (class "Default")
      (node (ref "IC-B3") (pin "15") (pinfunction "QA_15") (pintype "unspecified"))
      (node (ref "R129") (pin "2") (pinfunction "2_2") (pintype "unspecified"))
    )
    (net (code "218") (name "Out 0C") (class "Default")
      (node (ref "IC-C") (pin "15") (pinfunction "QA_15") (pintype "unspecified"))
      (node (ref "R17") (pin "2") (pinfunction "2_2") (pintype "unspecified"))
    )
    (net (code "219") (name "Out 0C2") (class "Default")
      (node (ref "IC-C2") (pin "15") (pinfunction "QA_15") (pintype "unspecified"))
      (node (ref "R104") (pin "2") (pinfunction "2_2") (pintype "unspecified"))
    )
    (net (code "220") (name "Out 0C3") (class "Default")
      (node (ref "IC-C3") (pin "15") (pinfunction "QA_15") (pintype "unspecified"))
      (node (ref "R137") (pin "2") (pinfunction "2_2") (pintype "unspecified"))
    )
    (net (code "221") (name "Out 0D") (class "Default")
      (node (ref "IC-D") (pin "15") (pinfunction "QA_15") (pintype "unspecified"))
      (node (ref "R25") (pin "2") (pinfunction "2_2") (pintype "unspecified"))
    )
    (net (code "222") (name "Out 0D2") (class "Default")
      (node (ref "IC-D2") (pin "15") (pinfunction "QA_15") (pintype "unspecified"))
      (node (ref "R96") (pin "2") (pinfunction "2_2") (pintype "unspecified"))
    )
    (net (code "223") (name "Out 0D3") (class "Default")
      (node (ref "IC-D3") (pin "15") (pinfunction "QA_15") (pintype "unspecified"))
      (node (ref "R145") (pin "2") (pinfunction "2_2") (pintype "unspecified"))
    )
    (net (code "224") (name "Out 0E") (class "Default")
      (node (ref "IC-E") (pin "15") (pinfunction "QA_15") (pintype "unspecified"))
      (node (ref "R33") (pin "2") (pinfunction "2_2") (pintype "unspecified"))
    )
    (net (code "225") (name "Out 0E2") (class "Default")
      (node (ref "IC-E2") (pin "15") (pinfunction "QA_15") (pintype "unspecified"))
      (node (ref "R88") (pin "2") (pinfunction "2_2") (pintype "unspecified"))
    )
    (net (code "226") (name "Out 0E3") (class "Default")
      (node (ref "IC-E3") (pin "15") (pinfunction "QA_15") (pintype "unspecified"))
      (node (ref "R153") (pin "2") (pinfunction "2_2") (pintype "unspecified"))
    )
    (net (code "227") (name "Out 0F") (class "Default")
      (node (ref "IC-F") (pin "15") (pinfunction "QA_15") (pintype "unspecified"))
      (node (ref "R41") (pin "2") (pinfunction "2_2") (pintype "unspecified"))
    )
    (net (code "228") (name "Out 0F2") (class "Default")
      (node (ref "IC-F2") (pin "15") (pinfunction "QA_15") (pintype "unspecified"))
      (node (ref "R80") (pin "2") (pinfunction "2_2") (pintype "unspecified"))
    )
    (net (code "229") (name "Out 0F3") (class "Default")
      (node (ref "IC-F3") (pin "15") (pinfunction "QA_15") (pintype "unspecified"))
      (node (ref "R161") (pin "2") (pinfunction "2_2") (pintype "unspecified"))
    )
    (net (code "230") (name "Out 0G") (class "Default")
      (node (ref "IC-G") (pin "15") (pinfunction "QA_15") (pintype "unspecified"))
      (node (ref "R49") (pin "2") (pinfunction "2_2") (pintype "unspecified"))
    )
    (net (code "231") (name "Out 0G2") (class "Default")
      (node (ref "IC-G2") (pin "15") (pinfunction "QA_15") (pintype "unspecified"))
      (node (ref "R72") (pin "2") (pinfunction "2_2") (pintype "unspecified"))
    )
    (net (code "232") (name "Out 0G3") (class "Default")
      (node (ref "IC-G3") (pin "15") (pinfunction "QA_15") (pintype "unspecified"))
      (node (ref "R169") (pin "2") (pinfunction "2_2") (pintype "unspecified"))
    )
    (net (code "233") (name "Out 0H") (class "Default")
      (node (ref "IC-H") (pin "15") (pinfunction "QA_15") (pintype "unspecified"))
      (node (ref "R57") (pin "2") (pinfunction "2_2") (pintype "unspecified"))
    )
    (net (code "234") (name "Out 0H2") (class "Default")
      (node (ref "IC-H2") (pin "15") (pinfunction "QA_15") (pintype "unspecified"))
      (node (ref "R64") (pin "2") (pinfunction "2_2") (pintype "unspecified"))
    )
    (net (code "235") (name "Out 0H3") (class "Default")
      (node (ref "IC-H3") (pin "15") (pinfunction "QA_15") (pintype "unspecified"))
      (node (ref "R177") (pin "2") (pinfunction "2_2") (pintype "unspecified"))
    )
    (net (code "236") (name "Out 1A") (class "Default")
      (node (ref "IC-A") (pin "1") (pinfunction "QB_1") (pintype "unspecified"))
      (node (ref "R2") (pin "2") (pinfunction "2_2") (pintype "unspecified"))
    )
    (net (code "237") (name "Out 1A2") (class "Default")
      (node (ref "IC-A2") (pin "1") (pinfunction "QB_1") (pintype "unspecified"))
      (node (ref "R119") (pin "2") (pinfunction "2_2") (pintype "unspecified"))
    )
    (net (code "238") (name "Out 1A3") (class "Default")
      (node (ref "IC-A3") (pin "1") (pinfunction "QB_1") (pintype "unspecified"))
      (node (ref "R122") (pin "2") (pinfunction "2_2") (pintype "unspecified"))
    )
    (net (code "239") (name "Out 1B") (class "Default")
      (node (ref "IC-B") (pin "1") (pinfunction "QB_1") (pintype "unspecified"))
      (node (ref "R10") (pin "2") (pinfunction "2_2") (pintype "unspecified"))
    )
    (net (code "240") (name "Out 1B2") (class "Default")
      (node (ref "IC-B2") (pin "1") (pinfunction "QB_1") (pintype "unspecified"))
      (node (ref "R111") (pin "2") (pinfunction "2_2") (pintype "unspecified"))
    )
    (net (code "241") (name "Out 1B3") (class "Default")
      (node (ref "IC-B3") (pin "1") (pinfunction "QB_1") (pintype "unspecified"))
      (node (ref "R130") (pin "2") (pinfunction "2_2") (pintype "unspecified"))
    )
    (net (code "242") (name "Out 1C") (class "Default")
      (node (ref "IC-C") (pin "1") (pinfunction "QB_1") (pintype "unspecified"))
      (node (ref "R18") (pin "2") (pinfunction "2_2") (pintype "unspecified"))
    )
    (net (code "243") (name "Out 1C2") (class "Default")
      (node (ref "IC-C2") (pin "1") (pinfunction "QB_1") (pintype "unspecified"))
      (node (ref "R103") (pin "2") (pinfunction "2_2") (pintype "unspecified"))
    )
    (net (code "244") (name "Out 1C3") (class "Default")
      (node (ref "IC-C3") (pin "1") (pinfunction "QB_1") (pintype "unspecified"))
      (node (ref "R138") (pin "2") (pinfunction "2_2") (pintype "unspecified"))
    )
    (net (code "245") (name "Out 1D") (class "Default")
      (node (ref "IC-D") (pin "1") (pinfunction "QB_1") (pintype "unspecified"))
      (node (ref "R26") (pin "2") (pinfunction "2_2") (pintype "unspecified"))
    )
    (net (code "246") (name "Out 1D2") (class "Default")
      (node (ref "IC-D2") (pin "1") (pinfunction "QB_1") (pintype "unspecified"))
      (node (ref "R95") (pin "2") (pinfunction "2_2") (pintype "unspecified"))
    )
    (net (code "247") (name "Out 1D3") (class "Default")
      (node (ref "IC-D3") (pin "1") (pinfunction "QB_1") (pintype "unspecified"))
      (node (ref "R146") (pin "2") (pinfunction "2_2") (pintype "unspecified"))
    )
    (net (code "248") (name "Out 1E") (class "Default")
      (node (ref "IC-E") (pin "1") (pinfunction "QB_1") (pintype "unspecified"))
      (node (ref "R34") (pin "2") (pinfunction "2_2") (pintype "unspecified"))
    )
    (net (code "249") (name "Out 1E2") (class "Default")
      (node (ref "IC-E2") (pin "1") (pinfunction "QB_1") (pintype "unspecified"))
      (node (ref "R87") (pin "2") (pinfunction "2_2") (pintype "unspecified"))
    )
    (net (code "250") (name "Out 1E3") (class "Default")
      (node (ref "IC-E3") (pin "1") (pinfunction "QB_1") (pintype "unspecified"))
      (node (ref "R154") (pin "2") (pinfunction "2_2") (pintype "unspecified"))
    )
    (net (code "251") (name "Out 1F") (class "Default")
      (node (ref "IC-F") (pin "1") (pinfunction "QB_1") (pintype "unspecified"))
      (node (ref "R42") (pin "2") (pinfunction "2_2") (pintype "unspecified"))
    )
    (net (code "252") (name "Out 1F2") (class "Default")
      (node (ref "IC-F2") (pin "1") (pinfunction "QB_1") (pintype "unspecified"))
      (node (ref "R79") (pin "2") (pinfunction "2_2") (pintype "unspecified"))
    )
    (net (code "253") (name "Out 1F3") (class "Default")
      (node (ref "IC-F3") (pin "1") (pinfunction "QB_1") (pintype "unspecified"))
      (node (ref "R162") (pin "2") (pinfunction "2_2") (pintype "unspecified"))
    )
    (net (code "254") (name "Out 1G") (class "Default")
      (node (ref "IC-G") (pin "1") (pinfunction "QB_1") (pintype "unspecified"))
      (node (ref "R50") (pin "2") (pinfunction "2_2") (pintype "unspecified"))
    )
    (net (code "255") (name "Out 1G2") (class "Default")
      (node (ref "IC-G2") (pin "1") (pinfunction "QB_1") (pintype "unspecified"))
      (node (ref "R71") (pin "2") (pinfunction "2_2") (pintype "unspecified"))
    )
    (net (code "256") (name "Out 1G3") (class "Default")
      (node (ref "IC-G3") (pin "1") (pinfunction "QB_1") (pintype "unspecified"))
      (node (ref "R170") (pin "2") (pinfunction "2_2") (pintype "unspecified"))
    )
    (net (code "257") (name "Out 1H") (class "Default")
      (node (ref "IC-H") (pin "1") (pinfunction "QB_1") (pintype "unspecified"))
      (node (ref "R58") (pin "2") (pinfunction "2_2") (pintype "unspecified"))
    )
    (net (code "258") (name "Out 1H2") (class "Default")
      (node (ref "IC-H2") (pin "1") (pinfunction "QB_1") (pintype "unspecified"))
      (node (ref "R63") (pin "2") (pinfunction "2_2") (pintype "unspecified"))
    )
    (net (code "259") (name "Out 1H3") (class "Default")
      (node (ref "IC-H3") (pin "1") (pinfunction "QB_1") (pintype "unspecified"))
      (node (ref "R178") (pin "2") (pinfunction "2_2") (pintype "unspecified"))
    )
    (net (code "260") (name "Out 2A") (class "Default")
      (node (ref "IC-A") (pin "2") (pinfunction "QC_2") (pintype "unspecified"))
      (node (ref "R3") (pin "2") (pinfunction "2_2") (pintype "unspecified"))
    )
    (net (code "261") (name "Out 2A2") (class "Default")
      (node (ref "IC-A2") (pin "2") (pinfunction "QC_2") (pintype "unspecified"))
      (node (ref "R118") (pin "2") (pinfunction "2_2") (pintype "unspecified"))
    )
    (net (code "262") (name "Out 2A3") (class "Default")
      (node (ref "IC-A3") (pin "2") (pinfunction "QC_2") (pintype "unspecified"))
      (node (ref "R123") (pin "2") (pinfunction "2_2") (pintype "unspecified"))
    )
    (net (code "263") (name "Out 2B") (class "Default")
      (node (ref "IC-B") (pin "2") (pinfunction "QC_2") (pintype "unspecified"))
      (node (ref "R11") (pin "2") (pinfunction "2_2") (pintype "unspecified"))
    )
    (net (code "264") (name "Out 2B2") (class "Default")
      (node (ref "IC-B2") (pin "2") (pinfunction "QC_2") (pintype "unspecified"))
      (node (ref "R110") (pin "2") (pinfunction "2_2") (pintype "unspecified"))
    )
    (net (code "265") (name "Out 2B3") (class "Default")
      (node (ref "IC-B3") (pin "2") (pinfunction "QC_2") (pintype "unspecified"))
      (node (ref "R131") (pin "2") (pinfunction "2_2") (pintype "unspecified"))
    )
    (net (code "266") (name "Out 2C") (class "Default")
      (node (ref "IC-C") (pin "2") (pinfunction "QC_2") (pintype "unspecified"))
      (node (ref "R19") (pin "2") (pinfunction "2_2") (pintype "unspecified"))
    )
    (net (code "267") (name "Out 2C2") (class "Default")
      (node (ref "IC-C2") (pin "2") (pinfunction "QC_2") (pintype "unspecified"))
      (node (ref "R102") (pin "2") (pinfunction "2_2") (pintype "unspecified"))
    )
    (net (code "268") (name "Out 2C3") (class "Default")
      (node (ref "IC-C3") (pin "2") (pinfunction "QC_2") (pintype "unspecified"))
      (node (ref "R139") (pin "2") (pinfunction "2_2") (pintype "unspecified"))
    )
    (net (code "269") (name "Out 2D") (class "Default")
      (node (ref "IC-D") (pin "2") (pinfunction "QC_2") (pintype "unspecified"))
      (node (ref "R27") (pin "2") (pinfunction "2_2") (pintype "unspecified"))
    )
    (net (code "270") (name "Out 2D2") (class "Default")
      (node (ref "IC-D2") (pin "2") (pinfunction "QC_2") (pintype "unspecified"))
      (node (ref "R94") (pin "2") (pinfunction "2_2") (pintype "unspecified"))
    )
    (net (code "271") (name "Out 2D3") (class "Default")
      (node (ref "IC-D3") (pin "2") (pinfunction "QC_2") (pintype "unspecified"))
      (node (ref "R147") (pin "2") (pinfunction "2_2") (pintype "unspecified"))
    )
    (net (code "272") (name "Out 2E") (class "Default")
      (node (ref "IC-E") (pin "2") (pinfunction "QC_2") (pintype "unspecified"))
      (node (ref "R35") (pin "2") (pinfunction "2_2") (pintype "unspecified"))
    )
    (net (code "273") (name "Out 2E2") (class "Default")
      (node (ref "IC-E2") (pin "2") (pinfunction "QC_2") (pintype "unspecified"))
      (node (ref "R86") (pin "2") (pinfunction "2_2") (pintype "unspecified"))
    )
    (net (code "274") (name "Out 2E3") (class "Default")
      (node (ref "IC-E3") (pin "2") (pinfunction "QC_2") (pintype "unspecified"))
      (node (ref "R155") (pin "2") (pinfunction "2_2") (pintype "unspecified"))
    )
    (net (code "275") (name "Out 2F") (class "Default")
      (node (ref "IC-F") (pin "2") (pinfunction "QC_2") (pintype "unspecified"))
      (node (ref "R43") (pin "2") (pinfunction "2_2") (pintype "unspecified"))
    )
    (net (code "276") (name "Out 2F2") (class "Default")
      (node (ref "IC-F2") (pin "2") (pinfunction "QC_2") (pintype "unspecified"))
      (node (ref "R78") (pin "2") (pinfunction "2_2") (pintype "unspecified"))
    )
    (net (code "277") (name "Out 2F3") (class "Default")
      (node (ref "IC-F3") (pin "2") (pinfunction "QC_2") (pintype "unspecified"))
      (node (ref "R163") (pin "2") (pinfunction "2_2") (pintype "unspecified"))
    )
    (net (code "278") (name "Out 2G") (class "Default")
      (node (ref "IC-G") (pin "2") (pinfunction "QC_2") (pintype "unspecified"))
      (node (ref "R51") (pin "2") (pinfunction "2_2") (pintype "unspecified"))
    )
    (net (code "279") (name "Out 2G2") (class "Default")
      (node (ref "IC-G2") (pin "2") (pinfunction "QC_2") (pintype "unspecified"))
      (node (ref "R70") (pin "2") (pinfunction "2_2") (pintype "unspecified"))
    )
    (net (code "280") (name "Out 2G3") (class "Default")
      (node (ref "IC-G3") (pin "2") (pinfunction "QC_2") (pintype "unspecified"))
      (node (ref "R171") (pin "2") (pinfunction "2_2") (pintype "unspecified"))
    )
    (net (code "281") (name "Out 2H") (class "Default")
      (node (ref "IC-H") (pin "2") (pinfunction "QC_2") (pintype "unspecified"))
      (node (ref "R59") (pin "2") (pinfunction "2_2") (pintype "unspecified"))
    )
    (net (code "282") (name "Out 2H2") (class "Default")
      (node (ref "IC-H2") (pin "2") (pinfunction "QC_2") (pintype "unspecified"))
      (node (ref "R62") (pin "2") (pinfunction "2_2") (pintype "unspecified"))
    )
    (net (code "283") (name "Out 2H3") (class "Default")
      (node (ref "IC-H3") (pin "2") (pinfunction "QC_2") (pintype "unspecified"))
      (node (ref "R179") (pin "2") (pinfunction "2_2") (pintype "unspecified"))
    )
    (net (code "284") (name "Out 3A") (class "Default")
      (node (ref "IC-A") (pin "3") (pinfunction "QD_3") (pintype "unspecified"))
      (node (ref "R4") (pin "2") (pinfunction "2_2") (pintype "unspecified"))
    )
    (net (code "285") (name "Out 3A2") (class "Default")
      (node (ref "IC-A2") (pin "3") (pinfunction "QD_3") (pintype "unspecified"))
      (node (ref "R117") (pin "2") (pinfunction "2_2") (pintype "unspecified"))
    )
    (net (code "286") (name "Out 3A3") (class "Default")
      (node (ref "IC-A3") (pin "3") (pinfunction "QD_3") (pintype "unspecified"))
      (node (ref "R124") (pin "2") (pinfunction "2_2") (pintype "unspecified"))
    )
    (net (code "287") (name "Out 3B") (class "Default")
      (node (ref "IC-B") (pin "3") (pinfunction "QD_3") (pintype "unspecified"))
      (node (ref "R12") (pin "2") (pinfunction "2_2") (pintype "unspecified"))
    )
    (net (code "288") (name "Out 3B2") (class "Default")
      (node (ref "IC-B2") (pin "3") (pinfunction "QD_3") (pintype "unspecified"))
      (node (ref "R109") (pin "2") (pinfunction "2_2") (pintype "unspecified"))
    )
    (net (code "289") (name "Out 3B3") (class "Default")
      (node (ref "IC-B3") (pin "3") (pinfunction "QD_3") (pintype "unspecified"))
      (node (ref "R132") (pin "2") (pinfunction "2_2") (pintype "unspecified"))
    )
    (net (code "290") (name "Out 3C") (class "Default")
      (node (ref "IC-C") (pin "3") (pinfunction "QD_3") (pintype "unspecified"))
      (node (ref "R20") (pin "2") (pinfunction "2_2") (pintype "unspecified"))
    )
    (net (code "291") (name "Out 3C2") (class "Default")
      (node (ref "IC-C2") (pin "3") (pinfunction "QD_3") (pintype "unspecified"))
      (node (ref "R101") (pin "2") (pinfunction "2_2") (pintype "unspecified"))
    )
    (net (code "292") (name "Out 3C3") (class "Default")
      (node (ref "IC-C3") (pin "3") (pinfunction "QD_3") (pintype "unspecified"))
      (node (ref "R140") (pin "2") (pinfunction "2_2") (pintype "unspecified"))
    )
    (net (code "293") (name "Out 3D") (class "Default")
      (node (ref "IC-D") (pin "3") (pinfunction "QD_3") (pintype "unspecified"))
      (node (ref "R28") (pin "2") (pinfunction "2_2") (pintype "unspecified"))
    )
    (net (code "294") (name "Out 3D2") (class "Default")
      (node (ref "IC-D2") (pin "3") (pinfunction "QD_3") (pintype "unspecified"))
      (node (ref "R93") (pin "2") (pinfunction "2_2") (pintype "unspecified"))
    )
    (net (code "295") (name "Out 3D3") (class "Default")
      (node (ref "IC-D3") (pin "3") (pinfunction "QD_3") (pintype "unspecified"))
      (node (ref "R148") (pin "2") (pinfunction "2_2") (pintype "unspecified"))
    )
    (net (code "296") (name "Out 3E") (class "Default")
      (node (ref "IC-E") (pin "3") (pinfunction "QD_3") (pintype "unspecified"))
      (node (ref "R36") (pin "2") (pinfunction "2_2") (pintype "unspecified"))
    )
    (net (code "297") (name "Out 3E2") (class "Default")
      (node (ref "IC-E2") (pin "3") (pinfunction "QD_3") (pintype "unspecified"))
      (node (ref "R85") (pin "2") (pinfunction "2_2") (pintype "unspecified"))
    )
    (net (code "298") (name "Out 3E3") (class "Default")
      (node (ref "IC-E3") (pin "3") (pinfunction "QD_3") (pintype "unspecified"))
      (node (ref "R156") (pin "2") (pinfunction "2_2") (pintype "unspecified"))
    )
    (net (code "299") (name "Out 3F") (class "Default")
      (node (ref "IC-F") (pin "3") (pinfunction "QD_3") (pintype "unspecified"))
      (node (ref "R44") (pin "2") (pinfunction "2_2") (pintype "unspecified"))
    )
    (net (code "300") (name "Out 3F2") (class "Default")
      (node (ref "IC-F2") (pin "3") (pinfunction "QD_3") (pintype "unspecified"))
      (node (ref "R77") (pin "2") (pinfunction "2_2") (pintype "unspecified"))
    )
    (net (code "301") (name "Out 3F3") (class "Default")
      (node (ref "IC-F3") (pin "3") (pinfunction "QD_3") (pintype "unspecified"))
      (node (ref "R164") (pin "2") (pinfunction "2_2") (pintype "unspecified"))
    )
    (net (code "302") (name "Out 3G") (class "Default")
      (node (ref "IC-G") (pin "3") (pinfunction "QD_3") (pintype "unspecified"))
      (node (ref "R52") (pin "2") (pinfunction "2_2") (pintype "unspecified"))
    )
    (net (code "303") (name "Out 3G2") (class "Default")
      (node (ref "IC-G2") (pin "3") (pinfunction "QD_3") (pintype "unspecified"))
      (node (ref "R69") (pin "2") (pinfunction "2_2") (pintype "unspecified"))
    )
    (net (code "304") (name "Out 3G3") (class "Default")
      (node (ref "IC-G3") (pin "3") (pinfunction "QD_3") (pintype "unspecified"))
      (node (ref "R172") (pin "2") (pinfunction "2_2") (pintype "unspecified"))
    )
    (net (code "305") (name "Out 3H") (class "Default")
      (node (ref "IC-H") (pin "3") (pinfunction "QD_3") (pintype "unspecified"))
      (node (ref "R60") (pin "2") (pinfunction "2_2") (pintype "unspecified"))
    )
    (net (code "306") (name "Out 3H2") (class "Default")
      (node (ref "IC-H2") (pin "3") (pinfunction "QD_3") (pintype "unspecified"))
      (node (ref "R61") (pin "2") (pinfunction "2_2") (pintype "unspecified"))
    )
    (net (code "307") (name "Out 3H3") (class "Default")
      (node (ref "IC-H3") (pin "3") (pinfunction "QD_3") (pintype "unspecified"))
      (node (ref "R180") (pin "2") (pinfunction "2_2") (pintype "unspecified"))
    )
    (net (code "308") (name "Out 4A") (class "Default")
      (node (ref "IC-A") (pin "4") (pinfunction "QE_4") (pintype "unspecified"))
      (node (ref "R5") (pin "2") (pinfunction "2_2") (pintype "unspecified"))
    )
    (net (code "309") (name "Out 4A2") (class "Default")
      (node (ref "IC-A2") (pin "4") (pinfunction "QE_4") (pintype "unspecified"))
      (node (ref "R116") (pin "2") (pinfunction "2_2") (pintype "unspecified"))
    )
    (net (code "310") (name "Out 4A3") (class "Default")
      (node (ref "IC-A3") (pin "4") (pinfunction "QE_4") (pintype "unspecified"))
      (node (ref "R125") (pin "2") (pinfunction "2_2") (pintype "unspecified"))
    )
    (net (code "311") (name "Out 4B") (class "Default")
      (node (ref "IC-B") (pin "4") (pinfunction "QE_4") (pintype "unspecified"))
      (node (ref "R13") (pin "2") (pinfunction "2_2") (pintype "unspecified"))
    )
    (net (code "312") (name "Out 4B2") (class "Default")
      (node (ref "IC-B2") (pin "4") (pinfunction "QE_4") (pintype "unspecified"))
      (node (ref "R108") (pin "2") (pinfunction "2_2") (pintype "unspecified"))
    )
    (net (code "313") (name "Out 4B3") (class "Default")
      (node (ref "IC-B3") (pin "4") (pinfunction "QE_4") (pintype "unspecified"))
      (node (ref "R133") (pin "2") (pinfunction "2_2") (pintype "unspecified"))
    )
    (net (code "314") (name "Out 4C") (class "Default")
      (node (ref "IC-C") (pin "4") (pinfunction "QE_4") (pintype "unspecified"))
      (node (ref "R21") (pin "2") (pinfunction "2_2") (pintype "unspecified"))
    )
    (net (code "315") (name "Out 4C2") (class "Default")
      (node (ref "IC-C2") (pin "4") (pinfunction "QE_4") (pintype "unspecified"))
      (node (ref "R100") (pin "2") (pinfunction "2_2") (pintype "unspecified"))
    )
    (net (code "316") (name "Out 4C3") (class "Default")
      (node (ref "IC-C3") (pin "4") (pinfunction "QE_4") (pintype "unspecified"))
      (node (ref "R141") (pin "2") (pinfunction "2_2") (pintype "unspecified"))
    )
    (net (code "317") (name "Out 4D") (class "Default")
      (node (ref "IC-D") (pin "4") (pinfunction "QE_4") (pintype "unspecified"))
      (node (ref "R29") (pin "2") (pinfunction "2_2") (pintype "unspecified"))
    )
    (net (code "318") (name "Out 4D2") (class "Default")
      (node (ref "IC-D2") (pin "4") (pinfunction "QE_4") (pintype "unspecified"))
      (node (ref "R92") (pin "2") (pinfunction "2_2") (pintype "unspecified"))
    )
    (net (code "319") (name "Out 4D3") (class "Default")
      (node (ref "IC-D3") (pin "4") (pinfunction "QE_4") (pintype "unspecified"))
      (node (ref "R149") (pin "2") (pinfunction "2_2") (pintype "unspecified"))
    )
    (net (code "320") (name "Out 4E") (class "Default")
      (node (ref "IC-E") (pin "4") (pinfunction "QE_4") (pintype "unspecified"))
      (node (ref "R37") (pin "2") (pinfunction "2_2") (pintype "unspecified"))
    )
    (net (code "321") (name "Out 4E2") (class "Default")
      (node (ref "IC-E2") (pin "4") (pinfunction "QE_4") (pintype "unspecified"))
      (node (ref "R84") (pin "2") (pinfunction "2_2") (pintype "unspecified"))
    )
    (net (code "322") (name "Out 4E3") (class "Default")
      (node (ref "IC-E3") (pin "4") (pinfunction "QE_4") (pintype "unspecified"))
      (node (ref "R157") (pin "2") (pinfunction "2_2") (pintype "unspecified"))
    )
    (net (code "323") (name "Out 4F") (class "Default")
      (node (ref "IC-F") (pin "4") (pinfunction "QE_4") (pintype "unspecified"))
      (node (ref "R45") (pin "2") (pinfunction "2_2") (pintype "unspecified"))
    )
    (net (code "324") (name "Out 4F2") (class "Default")
      (node (ref "IC-F2") (pin "4") (pinfunction "QE_4") (pintype "unspecified"))
      (node (ref "R76") (pin "2") (pinfunction "2_2") (pintype "unspecified"))
    )
    (net (code "325") (name "Out 4F3") (class "Default")
      (node (ref "IC-F3") (pin "4") (pinfunction "QE_4") (pintype "unspecified"))
      (node (ref "R165") (pin "2") (pinfunction "2_2") (pintype "unspecified"))
    )
    (net (code "326") (name "Out 4G") (class "Default")
      (node (ref "IC-G") (pin "4") (pinfunction "QE_4") (pintype "unspecified"))
      (node (ref "R53") (pin "2") (pinfunction "2_2") (pintype "unspecified"))
    )
    (net (code "327") (name "Out 4G2") (class "Default")
      (node (ref "IC-G2") (pin "4") (pinfunction "QE_4") (pintype "unspecified"))
      (node (ref "R68") (pin "2") (pinfunction "2_2") (pintype "unspecified"))
    )
    (net (code "328") (name "Out 4G3") (class "Default")
      (node (ref "IC-G3") (pin "4") (pinfunction "QE_4") (pintype "unspecified"))
      (node (ref "R173") (pin "2") (pinfunction "2_2") (pintype "unspecified"))
    )
    (net (code "329") (name "Out 5A") (class "Default")
      (node (ref "IC-A") (pin "5") (pinfunction "QF_5") (pintype "unspecified"))
      (node (ref "R6") (pin "2") (pinfunction "2_2") (pintype "unspecified"))
    )
    (net (code "330") (name "Out 5A2") (class "Default")
      (node (ref "IC-A2") (pin "5") (pinfunction "QF_5") (pintype "unspecified"))
      (node (ref "R115") (pin "2") (pinfunction "2_2") (pintype "unspecified"))
    )
    (net (code "331") (name "Out 5A3") (class "Default")
      (node (ref "IC-A3") (pin "5") (pinfunction "QF_5") (pintype "unspecified"))
      (node (ref "R126") (pin "2") (pinfunction "2_2") (pintype "unspecified"))
    )
    (net (code "332") (name "Out 5B") (class "Default")
      (node (ref "IC-B") (pin "5") (pinfunction "QF_5") (pintype "unspecified"))
      (node (ref "R14") (pin "2") (pinfunction "2_2") (pintype "unspecified"))
    )
    (net (code "333") (name "Out 5B2") (class "Default")
      (node (ref "IC-B2") (pin "5") (pinfunction "QF_5") (pintype "unspecified"))
      (node (ref "R107") (pin "2") (pinfunction "2_2") (pintype "unspecified"))
    )
    (net (code "334") (name "Out 5B3") (class "Default")
      (node (ref "IC-B3") (pin "5") (pinfunction "QF_5") (pintype "unspecified"))
      (node (ref "R134") (pin "2") (pinfunction "2_2") (pintype "unspecified"))
    )
    (net (code "335") (name "Out 5C") (class "Default")
      (node (ref "IC-C") (pin "5") (pinfunction "QF_5") (pintype "unspecified"))
      (node (ref "R22") (pin "2") (pinfunction "2_2") (pintype "unspecified"))
    )
    (net (code "336") (name "Out 5C2") (class "Default")
      (node (ref "IC-C2") (pin "5") (pinfunction "QF_5") (pintype "unspecified"))
      (node (ref "R99") (pin "2") (pinfunction "2_2") (pintype "unspecified"))
    )
    (net (code "337") (name "Out 5C3") (class "Default")
      (node (ref "IC-C3") (pin "5") (pinfunction "QF_5") (pintype "unspecified"))
      (node (ref "R142") (pin "2") (pinfunction "2_2") (pintype "unspecified"))
    )
    (net (code "338") (name "Out 5D") (class "Default")
      (node (ref "IC-D") (pin "5") (pinfunction "QF_5") (pintype "unspecified"))
      (node (ref "R30") (pin "2") (pinfunction "2_2") (pintype "unspecified"))
    )
    (net (code "339") (name "Out 5D2") (class "Default")
      (node (ref "IC-D2") (pin "5") (pinfunction "QF_5") (pintype "unspecified"))
      (node (ref "R91") (pin "2") (pinfunction "2_2") (pintype "unspecified"))
    )
    (net (code "340") (name "Out 5D3") (class "Default")
      (node (ref "IC-D3") (pin "5") (pinfunction "QF_5") (pintype "unspecified"))
      (node (ref "R150") (pin "2") (pinfunction "2_2") (pintype "unspecified"))
    )
    (net (code "341") (name "Out 5E") (class "Default")
      (node (ref "IC-E") (pin "5") (pinfunction "QF_5") (pintype "unspecified"))
      (node (ref "R38") (pin "2") (pinfunction "2_2") (pintype "unspecified"))
    )
    (net (code "342") (name "Out 5E2") (class "Default")
      (node (ref "IC-E2") (pin "5") (pinfunction "QF_5") (pintype "unspecified"))
      (node (ref "R83") (pin "2") (pinfunction "2_2") (pintype "unspecified"))
    )
    (net (code "343") (name "Out 5E3") (class "Default")
      (node (ref "IC-E3") (pin "5") (pinfunction "QF_5") (pintype "unspecified"))
      (node (ref "R158") (pin "2") (pinfunction "2_2") (pintype "unspecified"))
    )
    (net (code "344") (name "Out 5F") (class "Default")
      (node (ref "IC-F") (pin "5") (pinfunction "QF_5") (pintype "unspecified"))
      (node (ref "R46") (pin "2") (pinfunction "2_2") (pintype "unspecified"))
    )
    (net (code "345") (name "Out 5F2") (class "Default")
      (node (ref "IC-F2") (pin "5") (pinfunction "QF_5") (pintype "unspecified"))
      (node (ref "R75") (pin "2") (pinfunction "2_2") (pintype "unspecified"))
    )
    (net (code "346") (name "Out 5F3") (class "Default")
      (node (ref "IC-F3") (pin "5") (pinfunction "QF_5") (pintype "unspecified"))
      (node (ref "R166") (pin "2") (pinfunction "2_2") (pintype "unspecified"))
    )
    (net (code "347") (name "Out 5G") (class "Default")
      (node (ref "IC-G") (pin "5") (pinfunction "QF_5") (pintype "unspecified"))
      (node (ref "R54") (pin "2") (pinfunction "2_2") (pintype "unspecified"))
    )
    (net (code "348") (name "Out 5G2") (class "Default")
      (node (ref "IC-G2") (pin "5") (pinfunction "QF_5") (pintype "unspecified"))
      (node (ref "R67") (pin "2") (pinfunction "2_2") (pintype "unspecified"))
    )
    (net (code "349") (name "Out 5G3") (class "Default")
      (node (ref "IC-G3") (pin "5") (pinfunction "QF_5") (pintype "unspecified"))
      (node (ref "R174") (pin "2") (pinfunction "2_2") (pintype "unspecified"))
    )
    (net (code "350") (name "Out 6A") (class "Default")
      (node (ref "IC-A") (pin "6") (pinfunction "QG_6") (pintype "unspecified"))
      (node (ref "R7") (pin "2") (pinfunction "2_2") (pintype "unspecified"))
    )
    (net (code "351") (name "Out 6A2") (class "Default")
      (node (ref "IC-A2") (pin "6") (pinfunction "QG_6") (pintype "unspecified"))
      (node (ref "R114") (pin "2") (pinfunction "2_2") (pintype "unspecified"))
    )
    (net (code "352") (name "Out 6A3") (class "Default")
      (node (ref "IC-A3") (pin "6") (pinfunction "QG_6") (pintype "unspecified"))
      (node (ref "R127") (pin "2") (pinfunction "2_2") (pintype "unspecified"))
    )
    (net (code "353") (name "Out 6B") (class "Default")
      (node (ref "IC-B") (pin "6") (pinfunction "QG_6") (pintype "unspecified"))
      (node (ref "R15") (pin "2") (pinfunction "2_2") (pintype "unspecified"))
    )
    (net (code "354") (name "Out 6B2") (class "Default")
      (node (ref "IC-B2") (pin "6") (pinfunction "QG_6") (pintype "unspecified"))
      (node (ref "R106") (pin "2") (pinfunction "2_2") (pintype "unspecified"))
    )
    (net (code "355") (name "Out 6B3") (class "Default")
      (node (ref "IC-B3") (pin "6") (pinfunction "QG_6") (pintype "unspecified"))
      (node (ref "R135") (pin "2") (pinfunction "2_2") (pintype "unspecified"))
    )
    (net (code "356") (name "Out 6C") (class "Default")
      (node (ref "IC-C") (pin "6") (pinfunction "QG_6") (pintype "unspecified"))
      (node (ref "R23") (pin "2") (pinfunction "2_2") (pintype "unspecified"))
    )
    (net (code "357") (name "Out 6C2") (class "Default")
      (node (ref "IC-C2") (pin "6") (pinfunction "QG_6") (pintype "unspecified"))
      (node (ref "R98") (pin "2") (pinfunction "2_2") (pintype "unspecified"))
    )
    (net (code "358") (name "Out 6C3") (class "Default")
      (node (ref "IC-C3") (pin "6") (pinfunction "QG_6") (pintype "unspecified"))
      (node (ref "R143") (pin "2") (pinfunction "2_2") (pintype "unspecified"))
    )
    (net (code "359") (name "Out 6D") (class "Default")
      (node (ref "IC-D") (pin "6") (pinfunction "QG_6") (pintype "unspecified"))
      (node (ref "R31") (pin "2") (pinfunction "2_2") (pintype "unspecified"))
    )
    (net (code "360") (name "Out 6D2") (class "Default")
      (node (ref "IC-D2") (pin "6") (pinfunction "QG_6") (pintype "unspecified"))
      (node (ref "R90") (pin "2") (pinfunction "2_2") (pintype "unspecified"))
    )
    (net (code "361") (name "Out 6D3") (class "Default")
      (node (ref "IC-D3") (pin "6") (pinfunction "QG_6") (pintype "unspecified"))
      (node (ref "R151") (pin "2") (pinfunction "2_2") (pintype "unspecified"))
    )
    (net (code "362") (name "Out 6E") (class "Default")
      (node (ref "IC-E") (pin "6") (pinfunction "QG_6") (pintype "unspecified"))
      (node (ref "R39") (pin "2") (pinfunction "2_2") (pintype "unspecified"))
    )
    (net (code "363") (name "Out 6E2") (class "Default")
      (node (ref "IC-E2") (pin "6") (pinfunction "QG_6") (pintype "unspecified"))
      (node (ref "R82") (pin "2") (pinfunction "2_2") (pintype "unspecified"))
    )
    (net (code "364") (name "Out 6E3") (class "Default")
      (node (ref "IC-E3") (pin "6") (pinfunction "QG_6") (pintype "unspecified"))
      (node (ref "R159") (pin "2") (pinfunction "2_2") (pintype "unspecified"))
    )
    (net (code "365") (name "Out 6F") (class "Default")
      (node (ref "IC-F") (pin "6") (pinfunction "QG_6") (pintype "unspecified"))
      (node (ref "R47") (pin "2") (pinfunction "2_2") (pintype "unspecified"))
    )
    (net (code "366") (name "Out 6F2") (class "Default")
      (node (ref "IC-F2") (pin "6") (pinfunction "QG_6") (pintype "unspecified"))
      (node (ref "R74") (pin "2") (pinfunction "2_2") (pintype "unspecified"))
    )
    (net (code "367") (name "Out 6F3") (class "Default")
      (node (ref "IC-F3") (pin "6") (pinfunction "QG_6") (pintype "unspecified"))
      (node (ref "R167") (pin "2") (pinfunction "2_2") (pintype "unspecified"))
    )
    (net (code "368") (name "Out 6G") (class "Default")
      (node (ref "IC-G") (pin "6") (pinfunction "QG_6") (pintype "unspecified"))
      (node (ref "R55") (pin "2") (pinfunction "2_2") (pintype "unspecified"))
    )
    (net (code "369") (name "Out 6G2") (class "Default")
      (node (ref "IC-G2") (pin "6") (pinfunction "QG_6") (pintype "unspecified"))
      (node (ref "R66") (pin "2") (pinfunction "2_2") (pintype "unspecified"))
    )
    (net (code "370") (name "Out 6G3") (class "Default")
      (node (ref "IC-G3") (pin "6") (pinfunction "QG_6") (pintype "unspecified"))
      (node (ref "R175") (pin "2") (pinfunction "2_2") (pintype "unspecified"))
    )
    (net (code "371") (name "Out 7A") (class "Default")
      (node (ref "IC-A") (pin "7") (pinfunction "QH_7") (pintype "unspecified"))
      (node (ref "R8") (pin "2") (pinfunction "2_2") (pintype "unspecified"))
    )
    (net (code "372") (name "Out 7A2") (class "Default")
      (node (ref "IC-A2") (pin "7") (pinfunction "QH_7") (pintype "unspecified"))
      (node (ref "R113") (pin "2") (pinfunction "2_2") (pintype "unspecified"))
    )
    (net (code "373") (name "Out 7A3") (class "Default")
      (node (ref "IC-A3") (pin "7") (pinfunction "QH_7") (pintype "unspecified"))
      (node (ref "R128") (pin "2") (pinfunction "2_2") (pintype "unspecified"))
    )
    (net (code "374") (name "Out 7B") (class "Default")
      (node (ref "IC-B") (pin "7") (pinfunction "QH_7") (pintype "unspecified"))
      (node (ref "R16") (pin "2") (pinfunction "2_2") (pintype "unspecified"))
    )
    (net (code "375") (name "Out 7B2") (class "Default")
      (node (ref "IC-B2") (pin "7") (pinfunction "QH_7") (pintype "unspecified"))
      (node (ref "R105") (pin "2") (pinfunction "2_2") (pintype "unspecified"))
    )
    (net (code "376") (name "Out 7B3") (class "Default")
      (node (ref "IC-B3") (pin "7") (pinfunction "QH_7") (pintype "unspecified"))
      (node (ref "R136") (pin "2") (pinfunction "2_2") (pintype "unspecified"))
    )
    (net (code "377") (name "Out 7C") (class "Default")
      (node (ref "IC-C") (pin "7") (pinfunction "QH_7") (pintype "unspecified"))
      (node (ref "R24") (pin "2") (pinfunction "2_2") (pintype "unspecified"))
    )
    (net (code "378") (name "Out 7C2") (class "Default")
      (node (ref "IC-C2") (pin "7") (pinfunction "QH_7") (pintype "unspecified"))
      (node (ref "R97") (pin "2") (pinfunction "2_2") (pintype "unspecified"))
    )
    (net (code "379") (name "Out 7C3") (class "Default")
      (node (ref "IC-C3") (pin "7") (pinfunction "QH_7") (pintype "unspecified"))
      (node (ref "R144") (pin "2") (pinfunction "2_2") (pintype "unspecified"))
    )
    (net (code "380") (name "Out 7D") (class "Default")
      (node (ref "IC-D") (pin "7") (pinfunction "QH_7") (pintype "unspecified"))
      (node (ref "R32") (pin "2") (pinfunction "2_2") (pintype "unspecified"))
    )
    (net (code "381") (name "Out 7D2") (class "Default")
      (node (ref "IC-D2") (pin "7") (pinfunction "QH_7") (pintype "unspecified"))
      (node (ref "R89") (pin "2") (pinfunction "2_2") (pintype "unspecified"))
    )
    (net (code "382") (name "Out 7D3") (class "Default")
      (node (ref "IC-D3") (pin "7") (pinfunction "QH_7") (pintype "unspecified"))
      (node (ref "R152") (pin "2") (pinfunction "2_2") (pintype "unspecified"))
    )
    (net (code "383") (name "Out 7E") (class "Default")
      (node (ref "IC-E") (pin "7") (pinfunction "QH_7") (pintype "unspecified"))
      (node (ref "R40") (pin "2") (pinfunction "2_2") (pintype "unspecified"))
    )
    (net (code "384") (name "Out 7E2") (class "Default")
      (node (ref "IC-E2") (pin "7") (pinfunction "QH_7") (pintype "unspecified"))
      (node (ref "R81") (pin "2") (pinfunction "2_2") (pintype "unspecified"))
    )
    (net (code "385") (name "Out 7E3") (class "Default")
      (node (ref "IC-E3") (pin "7") (pinfunction "QH_7") (pintype "unspecified"))
      (node (ref "R160") (pin "2") (pinfunction "2_2") (pintype "unspecified"))
    )
    (net (code "386") (name "Out 7F") (class "Default")
      (node (ref "IC-F") (pin "7") (pinfunction "QH_7") (pintype "unspecified"))
      (node (ref "R48") (pin "2") (pinfunction "2_2") (pintype "unspecified"))
    )
    (net (code "387") (name "Out 7F2") (class "Default")
      (node (ref "IC-F2") (pin "7") (pinfunction "QH_7") (pintype "unspecified"))
      (node (ref "R73") (pin "2") (pinfunction "2_2") (pintype "unspecified"))
    )
    (net (code "388") (name "Out 7F3") (class "Default")
      (node (ref "IC-F3") (pin "7") (pinfunction "QH_7") (pintype "unspecified"))
      (node (ref "R168") (pin "2") (pinfunction "2_2") (pintype "unspecified"))
    )
    (net (code "389") (name "Out 7G") (class "Default")
      (node (ref "IC-G") (pin "7") (pinfunction "QH_7") (pintype "unspecified"))
      (node (ref "R56") (pin "2") (pinfunction "2_2") (pintype "unspecified"))
    )
    (net (code "390") (name "Out 7G2") (class "Default")
      (node (ref "IC-G2") (pin "7") (pinfunction "QH_7") (pintype "unspecified"))
      (node (ref "R65") (pin "2") (pinfunction "2_2") (pintype "unspecified"))
    )
    (net (code "391") (name "Out 7G3") (class "Default")
      (node (ref "IC-G3") (pin "7") (pinfunction "QH_7") (pintype "unspecified"))
      (node (ref "R176") (pin "2") (pinfunction "2_2") (pintype "unspecified"))
    )
    (net (code "392") (name "VCC") (class "Default")
      (node (ref "IC-A") (pin "10") (pinfunction "SCLR#_10") (pintype "unspecified"))
      (node (ref "IC-A") (pin "16") (pinfunction "VCC_16") (pintype "unspecified"))
      (node (ref "IC-A2") (pin "10") (pinfunction "SCLR#_10") (pintype "unspecified"))
      (node (ref "IC-A2") (pin "16") (pinfunction "VCC_16") (pintype "unspecified"))
      (node (ref "IC-A3") (pin "10") (pinfunction "SCLR#_10") (pintype "unspecified"))
      (node (ref "IC-A3") (pin "16") (pinfunction "VCC_16") (pintype "unspecified"))
      (node (ref "IC-B") (pin "10") (pinfunction "SCLR#_10") (pintype "unspecified"))
      (node (ref "IC-B") (pin "16") (pinfunction "VCC_16") (pintype "unspecified"))
      (node (ref "IC-B2") (pin "10") (pinfunction "SCLR#_10") (pintype "unspecified"))
      (node (ref "IC-B2") (pin "16") (pinfunction "VCC_16") (pintype "unspecified"))
      (node (ref "IC-B3") (pin "10") (pinfunction "SCLR#_10") (pintype "unspecified"))
      (node (ref "IC-B3") (pin "16") (pinfunction "VCC_16") (pintype "unspecified"))
      (node (ref "IC-C") (pin "10") (pinfunction "SCLR#_10") (pintype "unspecified"))
      (node (ref "IC-C") (pin "16") (pinfunction "VCC_16") (pintype "unspecified"))
      (node (ref "IC-C2") (pin "10") (pinfunction "SCLR#_10") (pintype "unspecified"))
      (node (ref "IC-C2") (pin "16") (pinfunction "VCC_16") (pintype "unspecified"))
      (node (ref "IC-C3") (pin "10") (pinfunction "SCLR#_10") (pintype "unspecified"))
      (node (ref "IC-C3") (pin "16") (pinfunction "VCC_16") (pintype "unspecified"))
      (node (ref "IC-D") (pin "10") (pinfunction "SCLR#_10") (pintype "unspecified"))
      (node (ref "IC-D") (pin "16") (pinfunction "VCC_16") (pintype "unspecified"))
      (node (ref "IC-D2") (pin "10") (pinfunction "SCLR#_10") (pintype "unspecified"))
      (node (ref "IC-D2") (pin "16") (pinfunction "VCC_16") (pintype "unspecified"))
      (node (ref "IC-D3") (pin "10") (pinfunction "SCLR#_10") (pintype "unspecified"))
      (node (ref "IC-D3") (pin "16") (pinfunction "VCC_16") (pintype "unspecified"))
      (node (ref "IC-E") (pin "10") (pinfunction "SCLR#_10") (pintype "unspecified"))
      (node (ref "IC-E") (pin "16") (pinfunction "VCC_16") (pintype "unspecified"))
      (node (ref "IC-E2") (pin "10") (pinfunction "SCLR#_10") (pintype "unspecified"))
      (node (ref "IC-E2") (pin "16") (pinfunction "VCC_16") (pintype "unspecified"))
      (node (ref "IC-E3") (pin "10") (pinfunction "SCLR#_10") (pintype "unspecified"))
      (node (ref "IC-E3") (pin "16") (pinfunction "VCC_16") (pintype "unspecified"))
      (node (ref "IC-F") (pin "10") (pinfunction "SCLR#_10") (pintype "unspecified"))
      (node (ref "IC-F") (pin "16") (pinfunction "VCC_16") (pintype "unspecified"))
      (node (ref "IC-F2") (pin "10") (pinfunction "SCLR#_10") (pintype "unspecified"))
      (node (ref "IC-F2") (pin "16") (pinfunction "VCC_16") (pintype "unspecified"))
      (node (ref "IC-F3") (pin "10") (pinfunction "SCLR#_10") (pintype "unspecified"))
      (node (ref "IC-F3") (pin "16") (pinfunction "VCC_16") (pintype "unspecified"))
      (node (ref "IC-G") (pin "10") (pinfunction "SCLR#_10") (pintype "unspecified"))
      (node (ref "IC-G") (pin "16") (pinfunction "VCC_16") (pintype "unspecified"))
      (node (ref "IC-G2") (pin "10") (pinfunction "SCLR#_10") (pintype "unspecified"))
      (node (ref "IC-G2") (pin "16") (pinfunction "VCC_16") (pintype "unspecified"))
      (node (ref "IC-G3") (pin "10") (pinfunction "SCLR#_10") (pintype "unspecified"))
      (node (ref "IC-G3") (pin "16") (pinfunction "VCC_16") (pintype "unspecified"))
      (node (ref "IC-H") (pin "10") (pinfunction "SCLR#_10") (pintype "unspecified"))
      (node (ref "IC-H") (pin "16") (pinfunction "VCC_16") (pintype "unspecified"))
      (node (ref "IC-H2") (pin "10") (pinfunction "SCLR#_10") (pintype "unspecified"))
      (node (ref "IC-H2") (pin "16") (pinfunction "VCC_16") (pintype "unspecified"))
      (node (ref "IC-H3") (pin "10") (pinfunction "SCLR#_10") (pintype "unspecified"))
      (node (ref "IC-H3") (pin "16") (pinfunction "VCC_16") (pintype "unspecified"))
      (node (ref "J1") (pin "1") (pinfunction "1_1") (pintype "unspecified"))
      (node (ref "J1") (pin "2") (pinfunction "2_2") (pintype "unspecified"))
      (node (ref "J2") (pin "1") (pinfunction "1_1") (pintype "unspecified"))
      (node (ref "J2") (pin "2") (pinfunction "2_2") (pintype "unspecified"))
      (node (ref "J3") (pin "1") (pinfunction "1_1") (pintype "unspecified"))
      (node (ref "J3") (pin "2") (pinfunction "2_2") (pintype "unspecified"))
    )
    (net (code "393") (name "unconnected-(IC-H-QE-Pad4)") (class "Default")
      (node (ref "IC-H") (pin "4") (pinfunction "QE_4") (pintype "unspecified+no_connect"))
    )
    (net (code "394") (name "unconnected-(IC-H-QF-Pad5)") (class "Default")
      (node (ref "IC-H") (pin "5") (pinfunction "QF_5") (pintype "unspecified+no_connect"))
    )
    (net (code "395") (name "unconnected-(IC-H-QG-Pad6)") (class "Default")
      (node (ref "IC-H") (pin "6") (pinfunction "QG_6") (pintype "unspecified+no_connect"))
    )
    (net (code "396") (name "unconnected-(IC-H-QH#-Pad9)") (class "Default")
      (node (ref "IC-H") (pin "9") (pinfunction "QH#_9") (pintype "unspecified+no_connect"))
    )
    (net (code "397") (name "unconnected-(IC-H-QH-Pad7)") (class "Default")
      (node (ref "IC-H") (pin "7") (pinfunction "QH_7") (pintype "unspecified+no_connect"))
    )
    (net (code "398") (name "unconnected-(IC-H2-QE-Pad4)") (class "Default")
      (node (ref "IC-H2") (pin "4") (pinfunction "QE_4") (pintype "unspecified+no_connect"))
    )
    (net (code "399") (name "unconnected-(IC-H2-QF-Pad5)") (class "Default")
      (node (ref "IC-H2") (pin "5") (pinfunction "QF_5") (pintype "unspecified+no_connect"))
    )
    (net (code "400") (name "unconnected-(IC-H2-QG-Pad6)") (class "Default")
      (node (ref "IC-H2") (pin "6") (pinfunction "QG_6") (pintype "unspecified+no_connect"))
    )
    (net (code "401") (name "unconnected-(IC-H2-QH#-Pad9)") (class "Default")
      (node (ref "IC-H2") (pin "9") (pinfunction "QH#_9") (pintype "unspecified+no_connect"))
    )
    (net (code "402") (name "unconnected-(IC-H2-QH-Pad7)") (class "Default")
      (node (ref "IC-H2") (pin "7") (pinfunction "QH_7") (pintype "unspecified+no_connect"))
    )
    (net (code "403") (name "unconnected-(IC-H3-QE-Pad4)") (class "Default")
      (node (ref "IC-H3") (pin "4") (pinfunction "QE_4") (pintype "unspecified+no_connect"))
    )
    (net (code "404") (name "unconnected-(IC-H3-QF-Pad5)") (class "Default")
      (node (ref "IC-H3") (pin "5") (pinfunction "QF_5") (pintype "unspecified+no_connect"))
    )
    (net (code "405") (name "unconnected-(IC-H3-QG-Pad6)") (class "Default")
      (node (ref "IC-H3") (pin "6") (pinfunction "QG_6") (pintype "unspecified+no_connect"))
    )
    (net (code "406") (name "unconnected-(IC-H3-QH#-Pad9)") (class "Default")
      (node (ref "IC-H3") (pin "9") (pinfunction "QH#_9") (pintype "unspecified+no_connect"))
    )
    (net (code "407") (name "unconnected-(IC-H3-QH-Pad7)") (class "Default")
      (node (ref "IC-H3") (pin "7") (pinfunction "QH_7") (pintype "unspecified+no_connect"))
    )
    (net (code "408") (name "unconnected-(J1-Pad5)") (class "Default")
      (node (ref "J1") (pin "5") (pinfunction "5_5") (pintype "unspecified+no_connect"))
    )
    (net (code "409") (name "unconnected-(J2-Pad5)") (class "Default")
      (node (ref "J2") (pin "5") (pinfunction "5_5") (pintype "unspecified+no_connect"))
    )
    (net (code "410") (name "unconnected-(J3-Pad5)") (class "Default")
      (node (ref "J3") (pin "5") (pinfunction "5_5") (pintype "unspecified+no_connect"))
    )
  )
)
